# BMS_Master.net
KiCad netlist of a schematic drawn in EAGLE
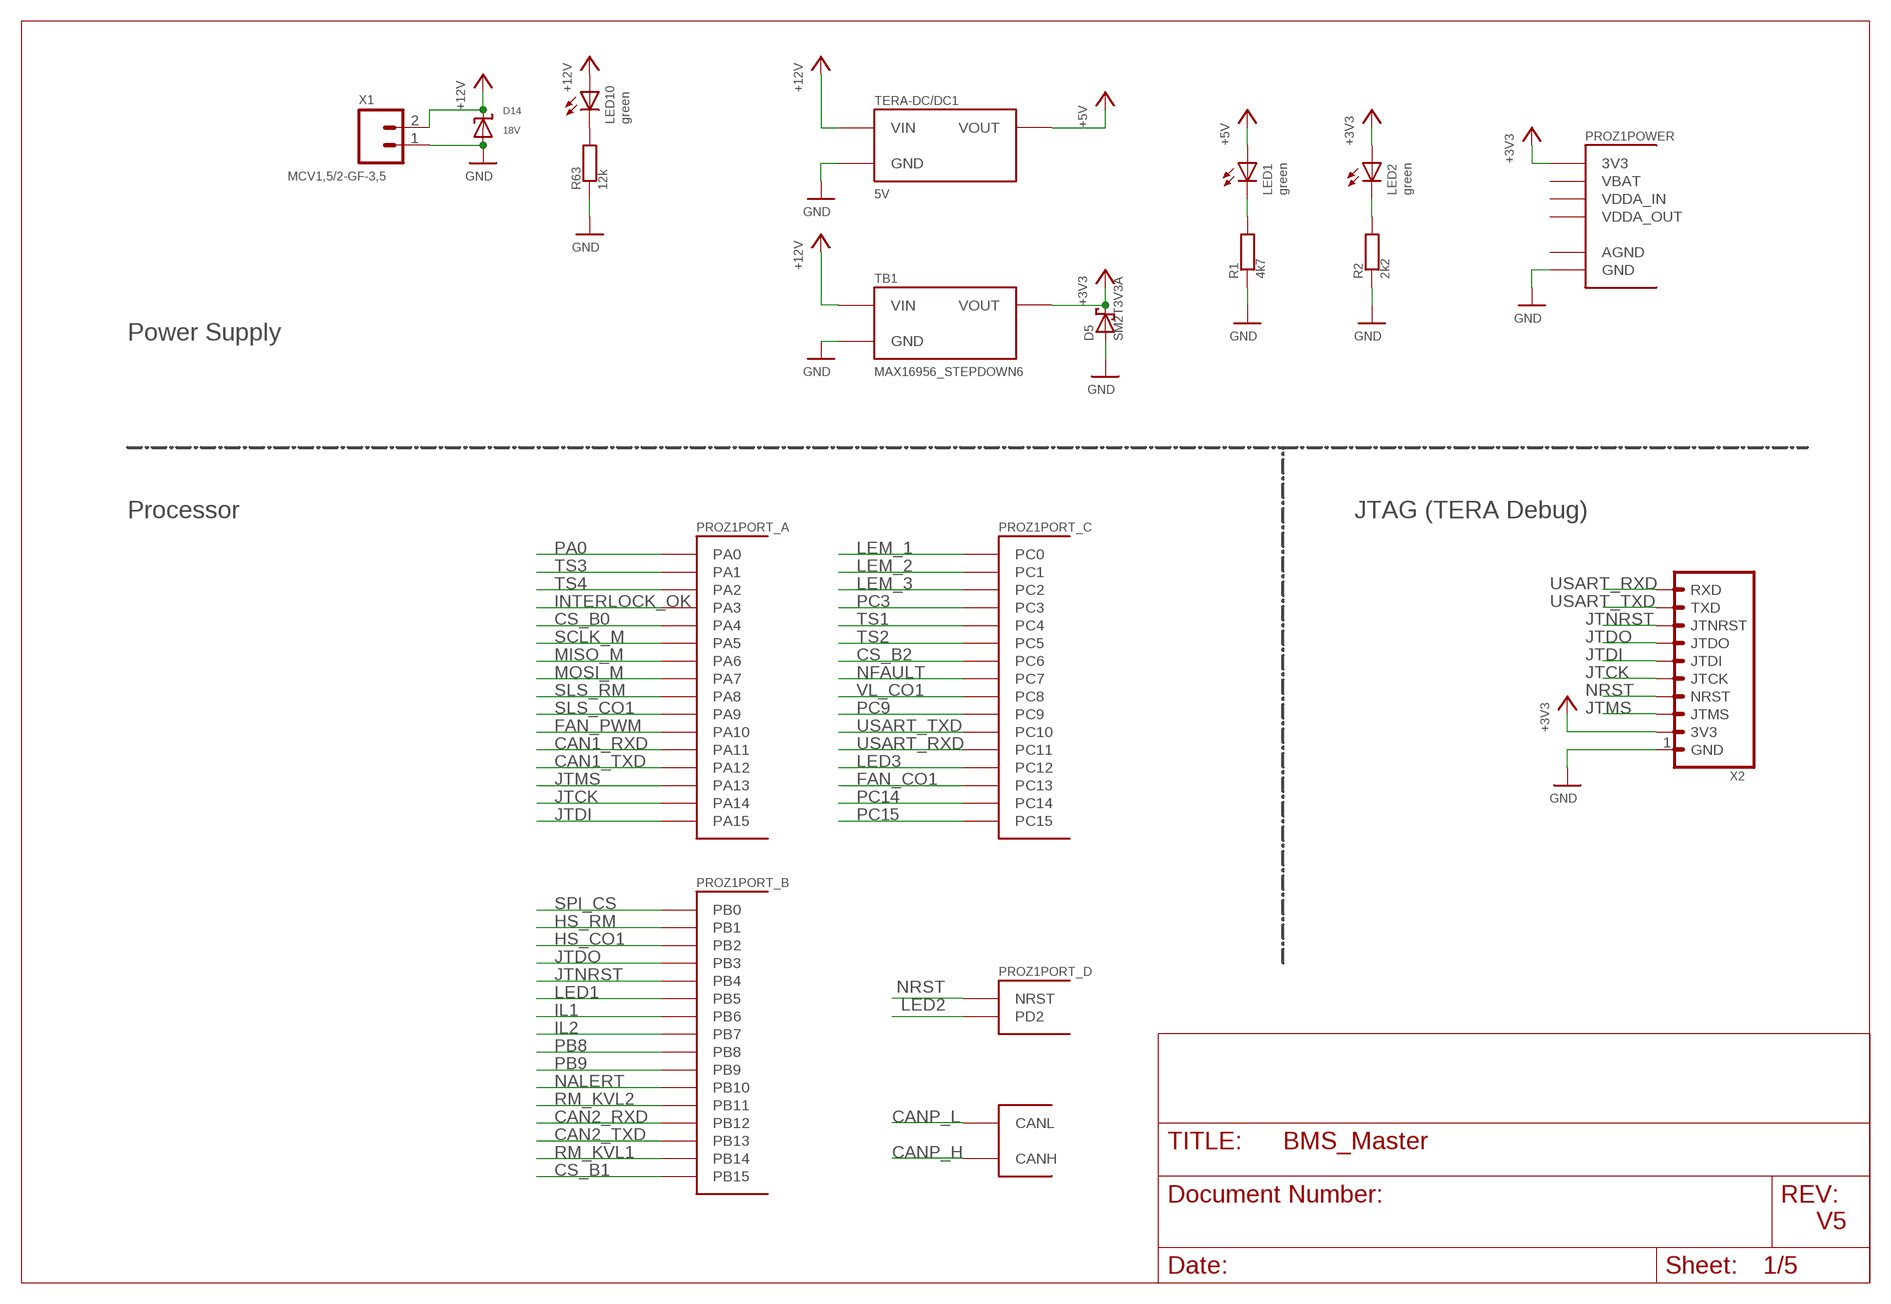
[diagram p0: schematic, sheet 1]
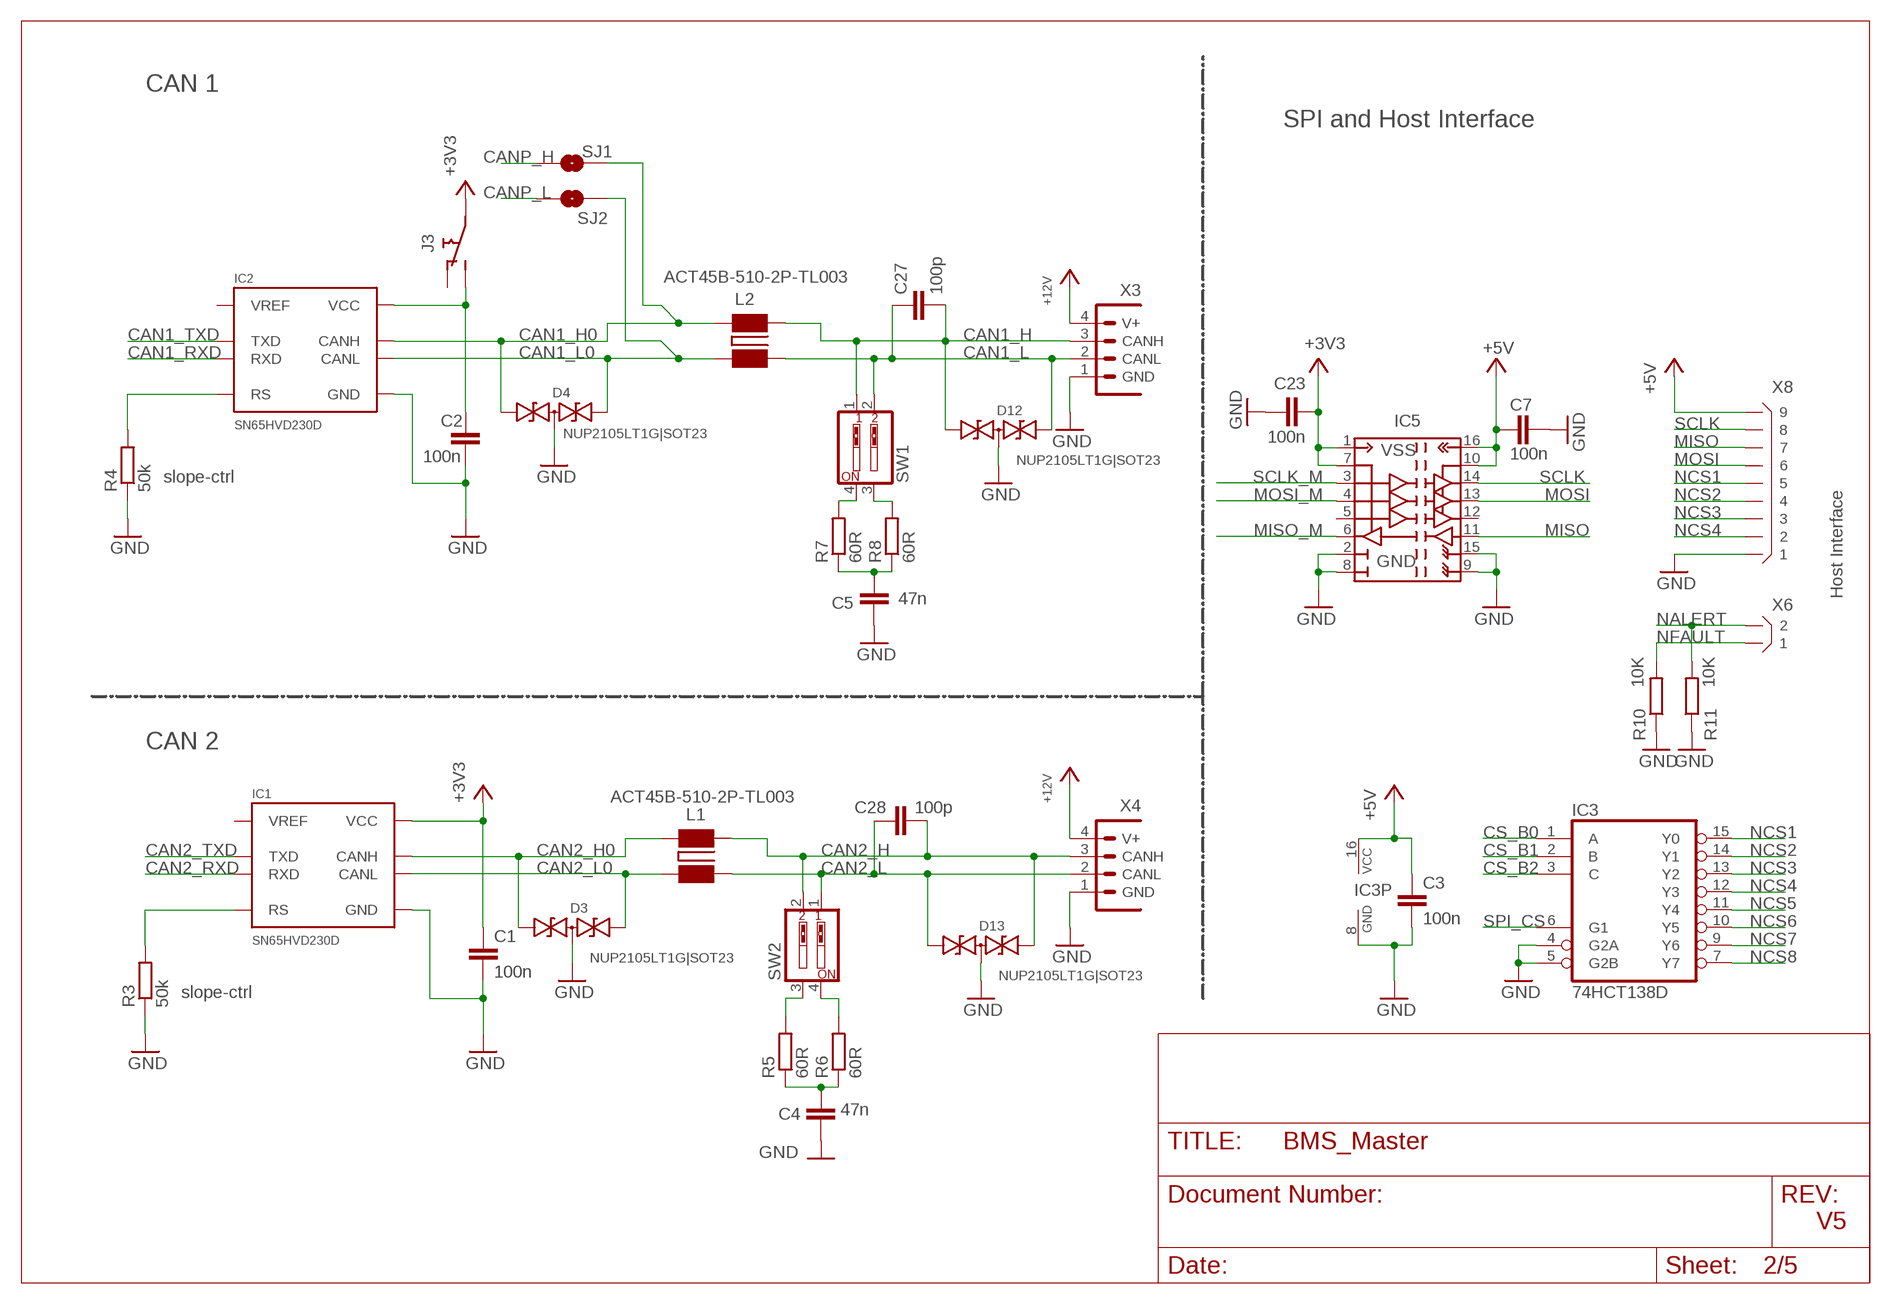
[diagram p1: schematic, sheet 2]
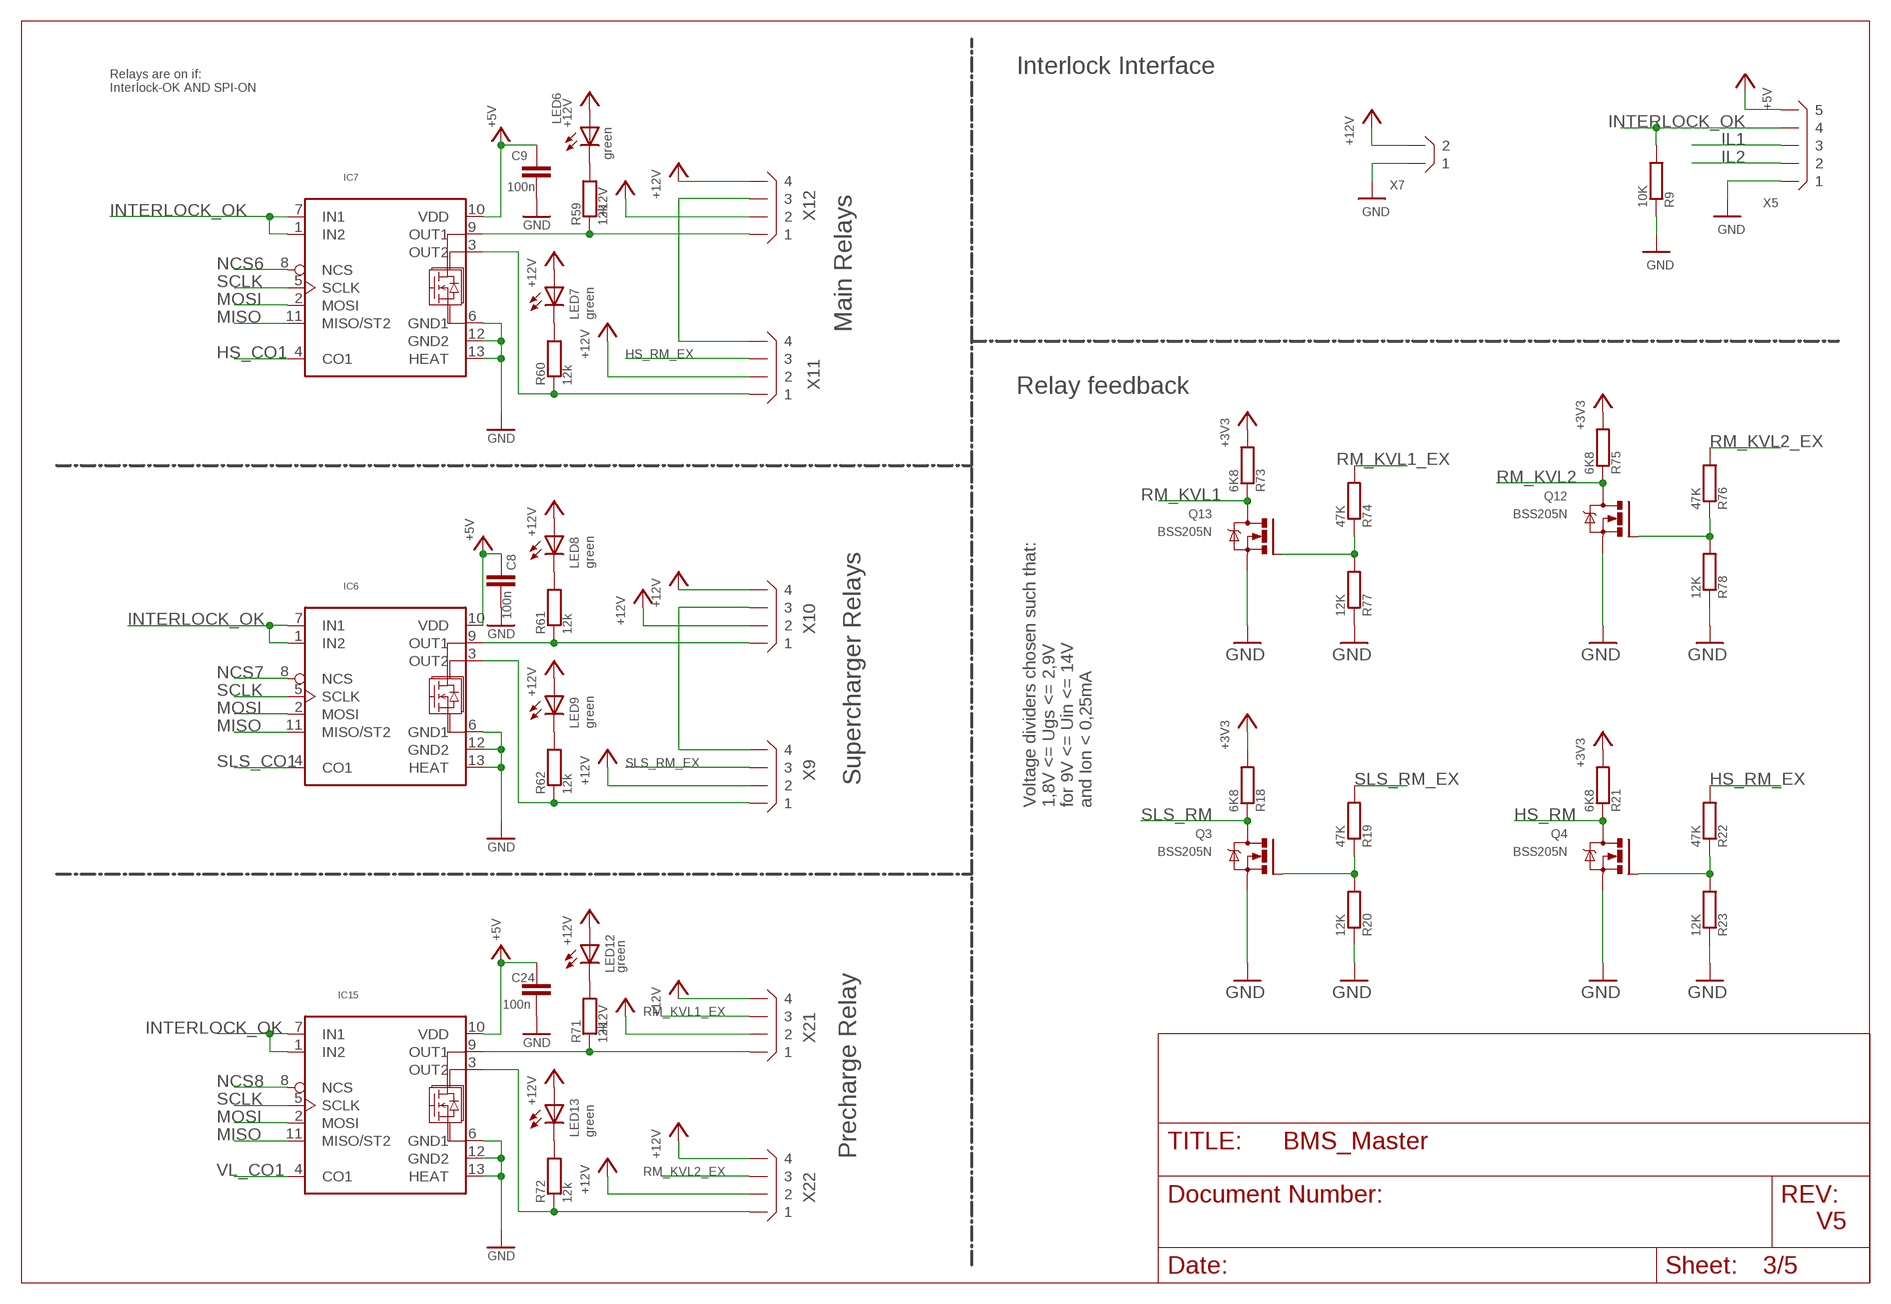
[diagram p2: schematic, sheet 3]
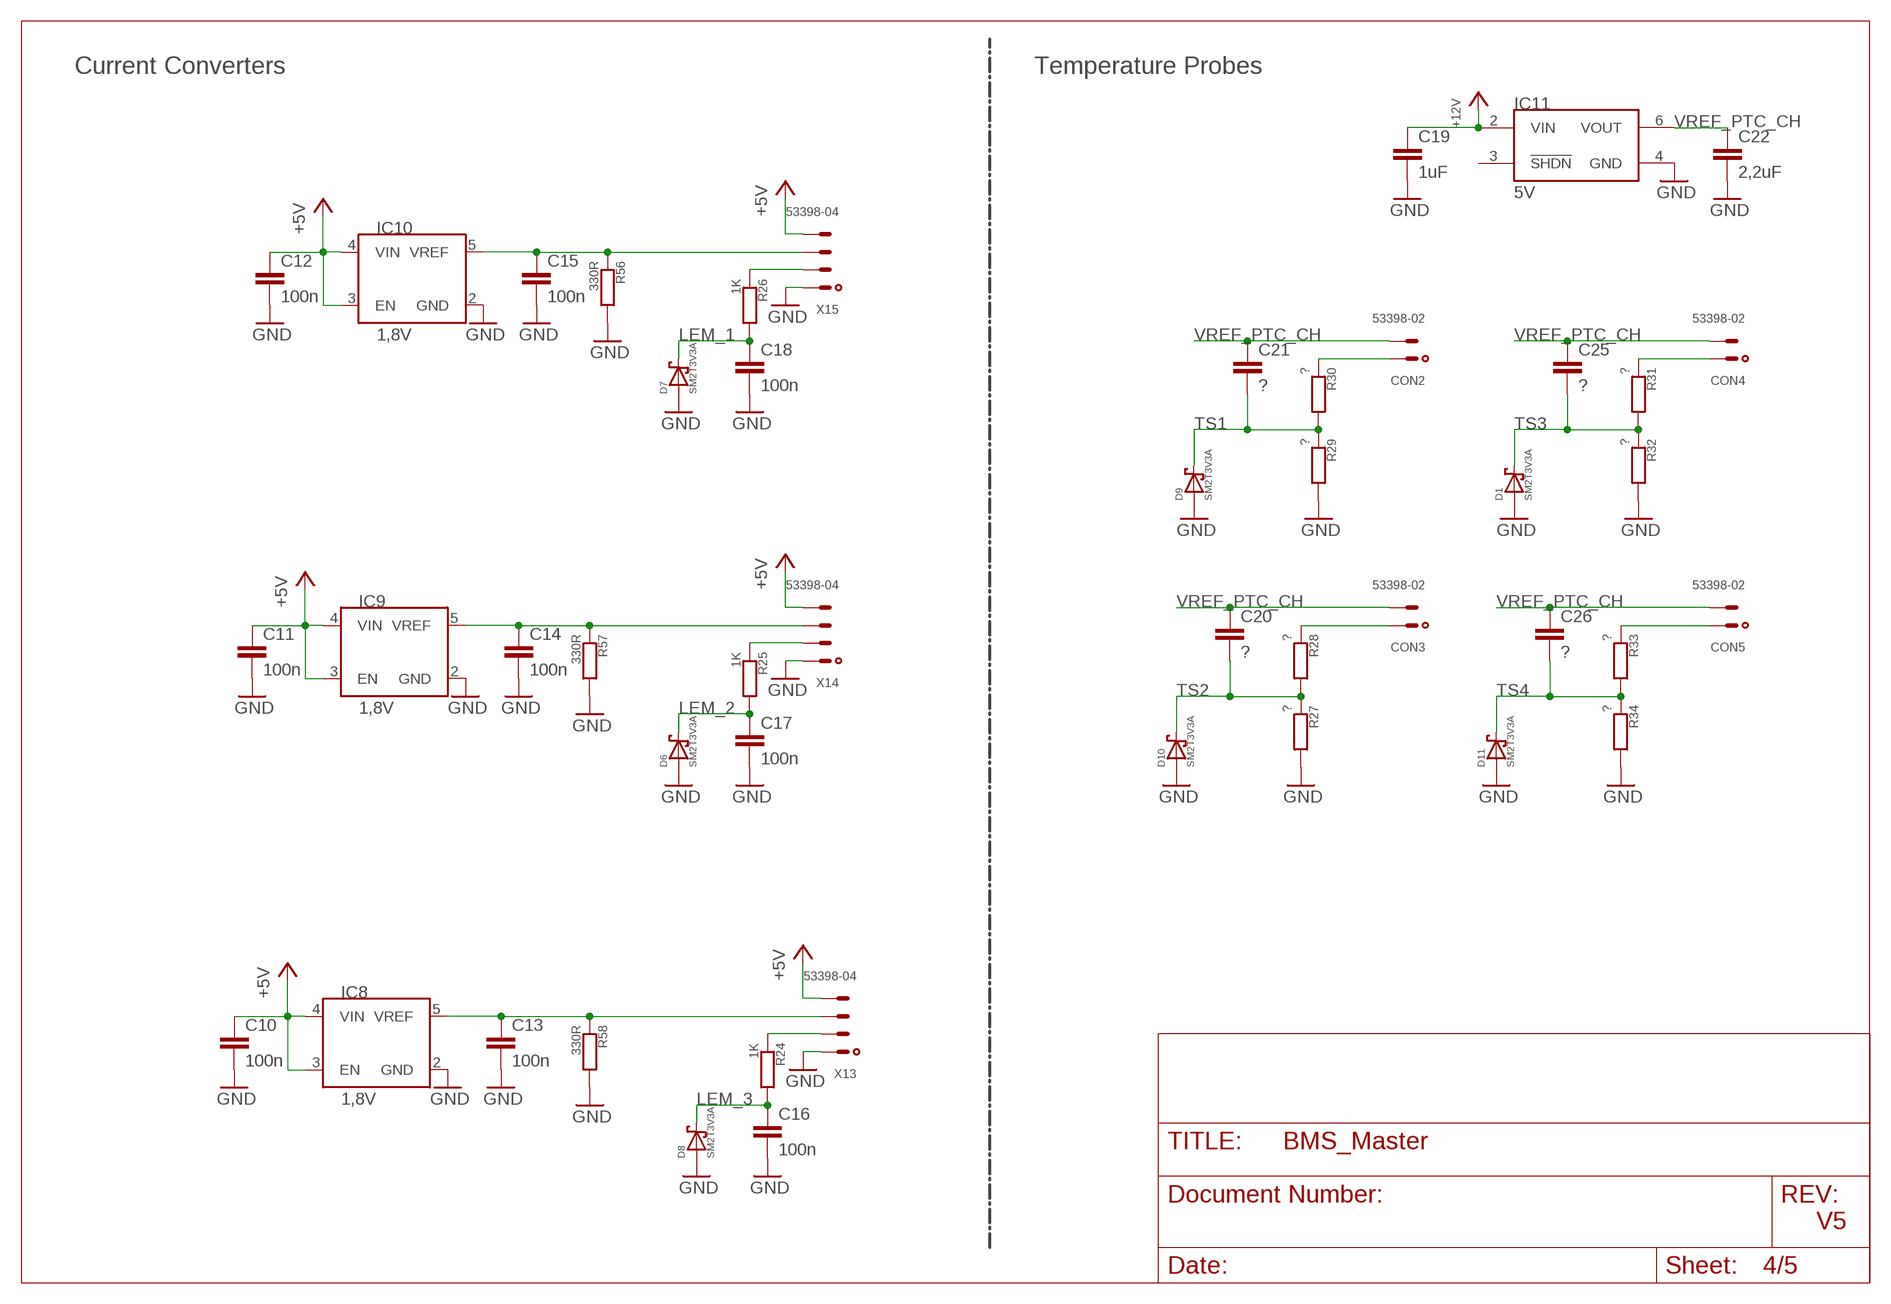
[diagram p3: schematic, sheet 4]
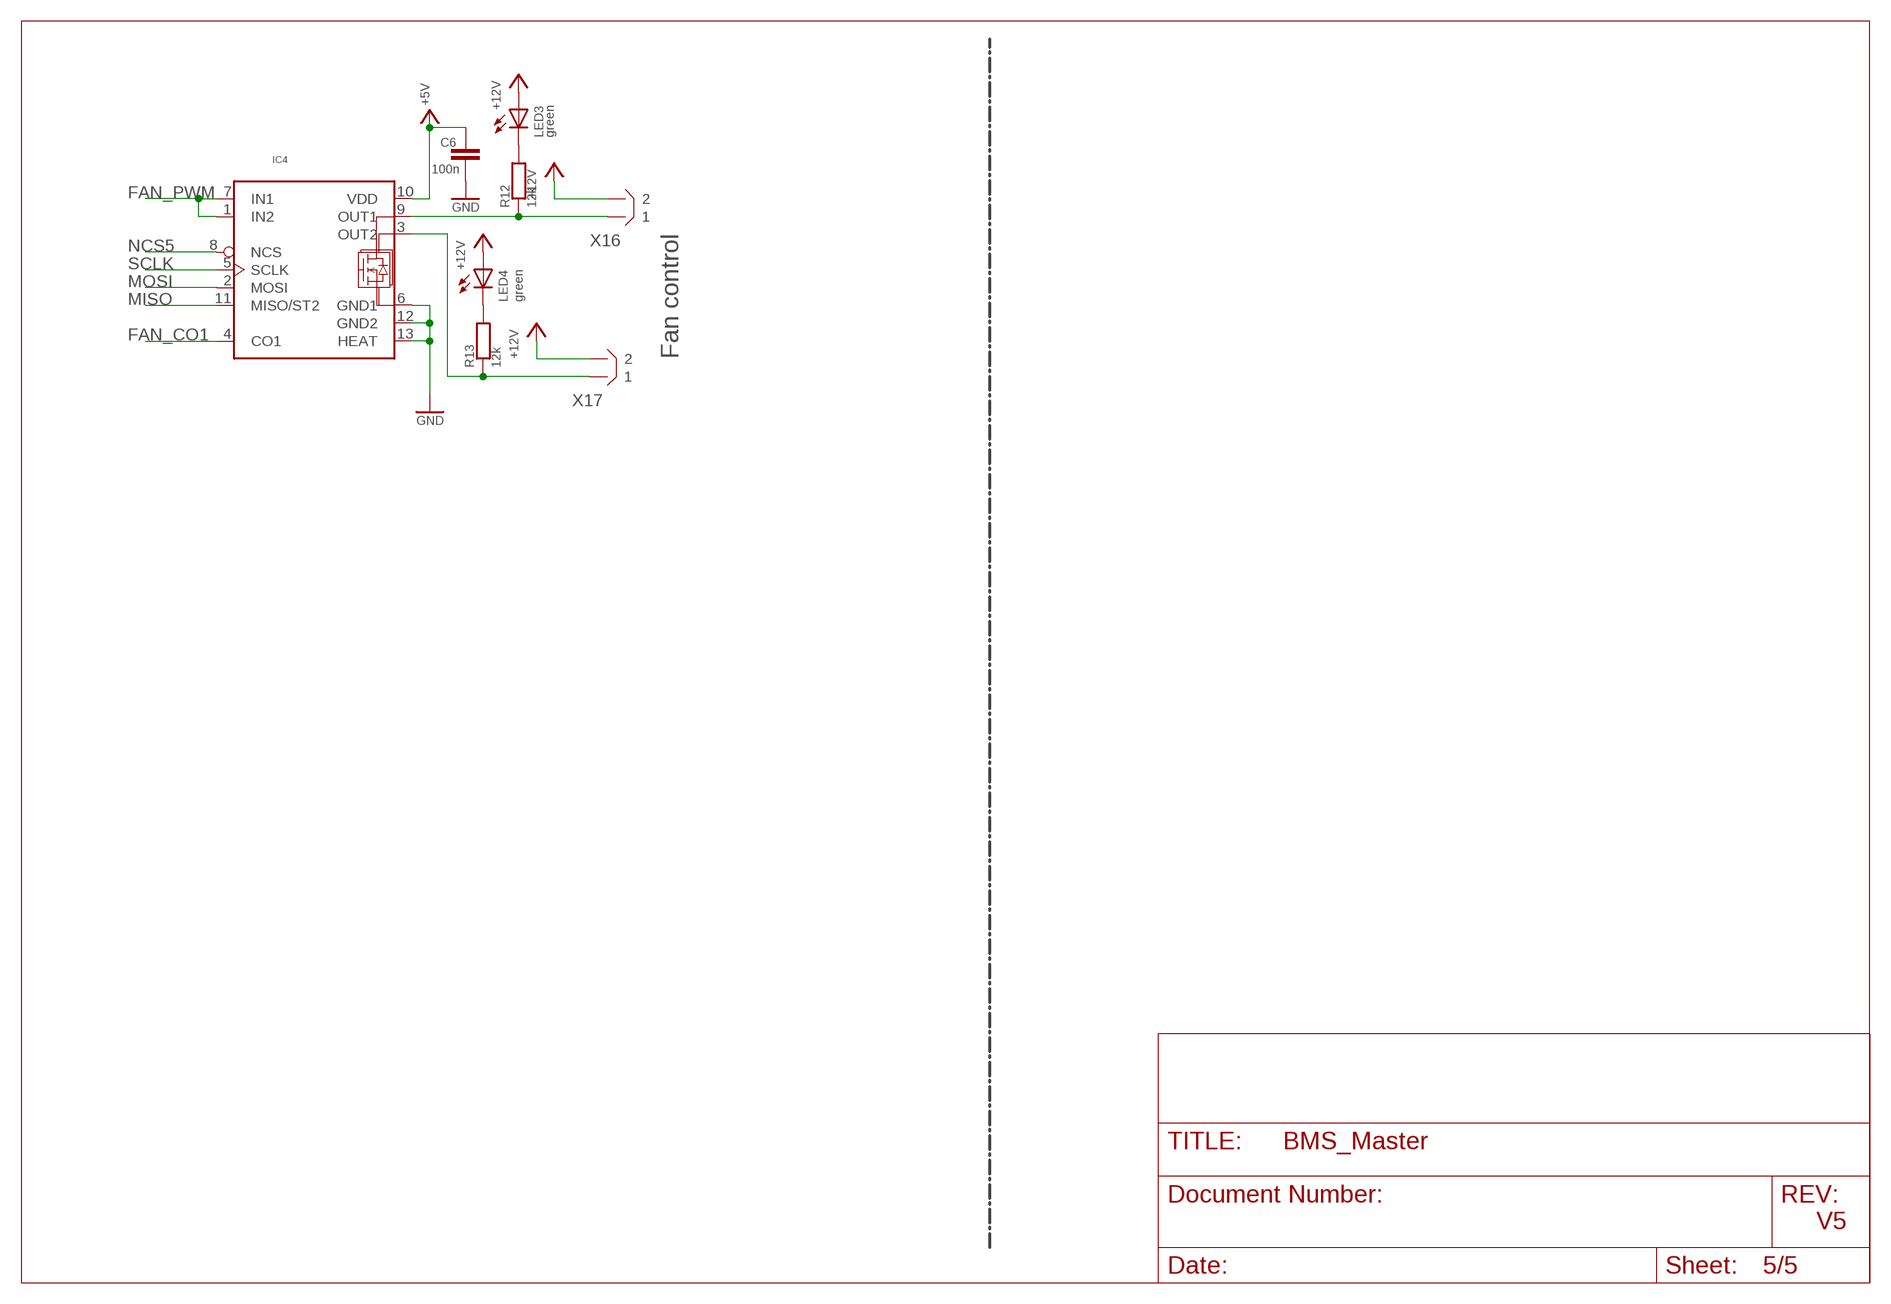
[diagram p4: schematic, sheet 5]

(export (version "E")
  (design (tool "Eeschema 10.0.6"))
  (components
    (comp (ref "C8")
      (value "100n")
      (footprint "eagle-import:C0603")
      (libsource (lib "eagle-import") (part "C-EUC0603"))
    )
    (comp (ref "C9")
      (value "100n")
      (footprint "eagle-import:C0603")
      (libsource (lib "eagle-import") (part "C-EUC0603"))
    )
    (comp (ref "C24")
      (value "100n")
      (footprint "eagle-import:C0603")
      (libsource (lib "eagle-import") (part "C-EUC0603"))
    )
    (comp (ref "IC6")
      (value "TLE8102SGN")
      (footprint "eagle-import:INF-PG-DSO-12-11_N_1PRIMARY")
      (libsource (lib "eagle-import") (part "TLE8102SGN"))
    )
    (comp (ref "IC7")
      (value "TLE8102SGN")
      (footprint "eagle-import:INF-PG-DSO-12-11_N_1PRIMARY")
      (libsource (lib "eagle-import") (part "TLE8102SGN"))
    )
    (comp (ref "IC15")
      (value "TLE8102SGN")
      (footprint "eagle-import:INF-PG-DSO-12-11_N_1PRIMARY")
      (libsource (lib "eagle-import") (part "TLE8102SGN"))
    )
    (comp (ref "LED6")
      (value "green")
      (footprint "eagle-import:CHIP-LED0805")
      (libsource (lib "eagle-import") (part "LEDCHIP-LED0805"))
    )
    (comp (ref "LED7")
      (value "green")
      (footprint "eagle-import:CHIP-LED0805")
      (libsource (lib "eagle-import") (part "LEDCHIP-LED0805"))
    )
    (comp (ref "LED8")
      (value "green")
      (footprint "eagle-import:CHIP-LED0805")
      (libsource (lib "eagle-import") (part "LEDCHIP-LED0805"))
    )
    (comp (ref "LED9")
      (value "green")
      (footprint "eagle-import:CHIP-LED0805")
      (libsource (lib "eagle-import") (part "LEDCHIP-LED0805"))
    )
    (comp (ref "LED12")
      (value "green")
      (footprint "eagle-import:CHIP-LED0805")
      (libsource (lib "eagle-import") (part "LEDCHIP-LED0805"))
    )
    (comp (ref "LED13")
      (value "green")
      (footprint "eagle-import:CHIP-LED0805")
      (libsource (lib "eagle-import") (part "LEDCHIP-LED0805"))
    )
    (comp (ref "Q3")
      (value "BSS205N")
      (footprint "eagle-import:SOT23")
      (libsource (lib "eagle-import") (part "BSS205N"))
    )
    (comp (ref "Q4")
      (value "BSS205N")
      (footprint "eagle-import:SOT23")
      (libsource (lib "eagle-import") (part "BSS205N"))
    )
    (comp (ref "Q12")
      (value "BSS205N")
      (footprint "eagle-import:SOT23")
      (libsource (lib "eagle-import") (part "BSS205N"))
    )
    (comp (ref "Q13")
      (value "BSS205N")
      (footprint "eagle-import:SOT23")
      (libsource (lib "eagle-import") (part "BSS205N"))
    )
    (comp (ref "R9")
      (value "10K")
      (footprint "eagle-import:R0805")
      (libsource (lib "eagle-import") (part "R"))
    )
    (comp (ref "R18")
      (value "6K8")
      (footprint "eagle-import:R0603")
      (libsource (lib "eagle-import") (part "R0603"))
    )
    (comp (ref "R19")
      (value "47K")
      (footprint "eagle-import:R0805")
      (libsource (lib "eagle-import") (part "R"))
    )
    (comp (ref "R20")
      (value "12K")
      (footprint "eagle-import:R0805")
      (libsource (lib "eagle-import") (part "R"))
    )
    (comp (ref "R21")
      (value "6K8")
      (footprint "eagle-import:R0603")
      (libsource (lib "eagle-import") (part "R0603"))
    )
    (comp (ref "R22")
      (value "47K")
      (footprint "eagle-import:R0805")
      (libsource (lib "eagle-import") (part "R"))
    )
    (comp (ref "R23")
      (value "12K")
      (footprint "eagle-import:R0805")
      (libsource (lib "eagle-import") (part "R"))
    )
    (comp (ref "R59")
      (value "12k")
      (footprint "eagle-import:R0805")
      (libsource (lib "eagle-import") (part "R"))
    )
    (comp (ref "R60")
      (value "12k")
      (footprint "eagle-import:R0805")
      (libsource (lib "eagle-import") (part "R"))
    )
    (comp (ref "R61")
      (value "12k")
      (footprint "eagle-import:R0805")
      (libsource (lib "eagle-import") (part "R"))
    )
    (comp (ref "R62")
      (value "12k")
      (footprint "eagle-import:R0805")
      (libsource (lib "eagle-import") (part "R"))
    )
    (comp (ref "R71")
      (value "12k")
      (footprint "eagle-import:R0805")
      (libsource (lib "eagle-import") (part "R"))
    )
    (comp (ref "R72")
      (value "12k")
      (footprint "eagle-import:R0805")
      (libsource (lib "eagle-import") (part "R"))
    )
    (comp (ref "R73")
      (value "6K8")
      (footprint "eagle-import:R0805")
      (libsource (lib "eagle-import") (part "R"))
    )
    (comp (ref "R74")
      (value "47K")
      (footprint "eagle-import:R0805")
      (libsource (lib "eagle-import") (part "R"))
    )
    (comp (ref "R75")
      (value "6K8")
      (footprint "eagle-import:R0805")
      (libsource (lib "eagle-import") (part "R"))
    )
    (comp (ref "R76")
      (value "47K")
      (footprint "eagle-import:R0805")
      (libsource (lib "eagle-import") (part "R"))
    )
    (comp (ref "R77")
      (value "12K")
      (footprint "eagle-import:R0805")
      (libsource (lib "eagle-import") (part "R"))
    )
    (comp (ref "R78")
      (value "12K")
      (footprint "eagle-import:R0805")
      (libsource (lib "eagle-import") (part "R"))
    )
    (comp (ref "X5")
      (value "B5B-XH")
      (footprint "eagle-import:B5B-XH")
      (libsource (lib "eagle-import") (part "?5B-XHB"))
    )
    (comp (ref "X7")
      (value "B2B-XH")
      (footprint "eagle-import:B2B-XH")
      (libsource (lib "eagle-import") (part "?2B-XHB"))
    )
    (comp (ref "X9")
      (value "B4B-XH")
      (footprint "eagle-import:B4B-XH")
      (libsource (lib "eagle-import") (part "?4B-XHB"))
    )
    (comp (ref "X10")
      (value "B4B-XH")
      (footprint "eagle-import:B4B-XH")
      (libsource (lib "eagle-import") (part "?4B-XHB"))
    )
    (comp (ref "X11")
      (value "B4B-XH")
      (footprint "eagle-import:B4B-XH")
      (libsource (lib "eagle-import") (part "?4B-XHB"))
    )
    (comp (ref "X12")
      (value "B4B-XH")
      (footprint "eagle-import:B4B-XH")
      (libsource (lib "eagle-import") (part "?4B-XHB"))
    )
    (comp (ref "X21")
      (value "B4B-XH")
      (footprint "eagle-import:B4B-XH")
      (libsource (lib "eagle-import") (part "?4B-XHB"))
    )
    (comp (ref "X22")
      (value "B4B-XH")
      (footprint "eagle-import:B4B-XH")
      (libsource (lib "eagle-import") (part "?4B-XHB"))
    )
    (comp (ref "C1")
      (value "100n")
      (footprint "eagle-import:C0805")
      (libsource (lib "eagle-import") (part "C-EUC0805"))
    )
    (comp (ref "C2")
      (value "100n")
      (footprint "eagle-import:C0805")
      (libsource (lib "eagle-import") (part "C-EUC0805"))
    )
    (comp (ref "C3")
      (value "100n")
      (footprint "eagle-import:C0805")
      (libsource (lib "eagle-import") (part "C-EUC0805"))
    )
    (comp (ref "C4")
      (value "47n")
      (footprint "eagle-import:C0603")
      (libsource (lib "eagle-import") (part "C-EUC0603"))
    )
    (comp (ref "C5")
      (value "47n")
      (footprint "eagle-import:C0603")
      (libsource (lib "eagle-import") (part "C-EUC0603"))
    )
    (comp (ref "C7")
      (value "100n")
      (footprint "eagle-import:C0603")
      (libsource (lib "eagle-import") (part "C0603"))
    )
    (comp (ref "C23")
      (value "100n")
      (footprint "eagle-import:C0603")
      (libsource (lib "eagle-import") (part "C0603"))
    )
    (comp (ref "C27")
      (value "100p")
      (footprint "eagle-import:C0603")
      (libsource (lib "eagle-import") (part "C-EUC0603"))
    )
    (comp (ref "C28")
      (value "100p")
      (footprint "eagle-import:C0603")
      (libsource (lib "eagle-import") (part "C-EUC0603"))
    )
    (comp (ref "D3")
      (value "NUP2105LT1G|SOT23")
      (footprint "eagle-import:SOT23")
      (libsource (lib "eagle-import") (part "NUP2105LT1G|SOT23"))
    )
    (comp (ref "D4")
      (value "NUP2105LT1G|SOT23")
      (footprint "eagle-import:SOT23")
      (libsource (lib "eagle-import") (part "NUP2105LT1G|SOT23"))
    )
    (comp (ref "D12")
      (value "NUP2105LT1G|SOT23")
      (footprint "eagle-import:SOT23")
      (libsource (lib "eagle-import") (part "NUP2105LT1G|SOT23"))
    )
    (comp (ref "D13")
      (value "NUP2105LT1G|SOT23")
      (footprint "eagle-import:SOT23")
      (libsource (lib "eagle-import") (part "NUP2105LT1G|SOT23"))
    )
    (comp (ref "IC1")
      (value "SN65HVD230D")
      (footprint "eagle-import:SO08")
      (libsource (lib "eagle-import") (part "SN65HVD23D0"))
    )
    (comp (ref "IC2")
      (value "SN65HVD230D")
      (footprint "eagle-import:SO08")
      (libsource (lib "eagle-import") (part "SN65HVD23D0"))
    )
    (comp (ref "IC3")
      (value "74HCT138D")
      (footprint "eagle-import:SO16")
      (libsource (lib "eagle-import") (part "74138DHCT"))
    )
    (comp (ref "IC5")
      (value "ISO7241")
      (footprint "eagle-import:R-PDSO-G16")
      (libsource (lib "eagle-import") (part "ISO7241"))
    )
    (comp (ref "J3")
      (value "JUMPER_SWITCHS")
      (footprint "eagle-import:J_OR_S")
      (libsource (lib "eagle-import") (part "JUMPER_SWITCHS"))
    )
    (comp (ref "L1")
      (value "ACT45B-510-2P-TL003")
      (footprint "eagle-import:ACT45B")
      (libsource (lib "eagle-import") (part "ACT45B-510-2P-TL003"))
    )
    (comp (ref "L2")
      (value "ACT45B-510-2P-TL003")
      (footprint "eagle-import:ACT45B")
      (libsource (lib "eagle-import") (part "ACT45B-510-2P-TL003"))
    )
    (comp (ref "R3")
      (value "50k")
      (footprint "eagle-import:R0805")
      (libsource (lib "eagle-import") (part "R-EU_R0805"))
    )
    (comp (ref "R4")
      (value "50k")
      (footprint "eagle-import:R0805")
      (libsource (lib "eagle-import") (part "R-EU_R0805"))
    )
    (comp (ref "R5")
      (value "60R")
      (footprint "eagle-import:R0603")
      (libsource (lib "eagle-import") (part "R-EU_R0603"))
    )
    (comp (ref "R6")
      (value "60R")
      (footprint "eagle-import:R0603")
      (libsource (lib "eagle-import") (part "R-EU_R0603"))
    )
    (comp (ref "R7")
      (value "60R")
      (footprint "eagle-import:R0603")
      (libsource (lib "eagle-import") (part "R-EU_R0603"))
    )
    (comp (ref "R8")
      (value "60R")
      (footprint "eagle-import:R0603")
      (libsource (lib "eagle-import") (part "R-EU_R0603"))
    )
    (comp (ref "R10")
      (value "10K")
      (footprint "eagle-import:R0603")
      (libsource (lib "eagle-import") (part "R-EU_R0603"))
    )
    (comp (ref "R11")
      (value "10K")
      (footprint "eagle-import:R0603")
      (libsource (lib "eagle-import") (part "R-EU_R0603"))
    )
    (comp (ref "SJ1")
      (value "SOLDERJUMPERNO")
      (footprint "eagle-import:SJ_2S-NO")
      (libsource (lib "eagle-import") (part "SOLDERJUMPERNO"))
    )
    (comp (ref "SJ2")
      (value "SOLDERJUMPERNO")
      (footprint "eagle-import:SJ_2S-NO")
      (libsource (lib "eagle-import") (part "SOLDERJUMPERNO"))
    )
    (comp (ref "SW1")
      (value "DIP_SWITCH_DIP2")
      (footprint "eagle-import:DIPSWITCH-02")
      (libsource (lib "eagle-import") (part "DIP_SWITCH_DIP2"))
    )
    (comp (ref "SW2")
      (value "DIP_SWITCH_DIP2")
      (footprint "eagle-import:DIPSWITCH-02")
      (libsource (lib "eagle-import") (part "DIP_SWITCH_DIP2"))
    )
    (comp (ref "X3")
      (value "CIOC_4-1-FV-A_CAN-BELEGUNG")
      (footprint "eagle-import:CIOC_4-1-FV")
      (libsource (lib "eagle-import") (part "CIOC_4-1-FV-A_CAN-BELEGUNG"))
    )
    (comp (ref "X4")
      (value "CIOC_4-1-FV-A_CAN-BELEGUNG")
      (footprint "eagle-import:CIOC_4-1-FV")
      (libsource (lib "eagle-import") (part "CIOC_4-1-FV-A_CAN-BELEGUNG"))
    )
    (comp (ref "X6")
      (value "B2B-XH")
      (footprint "eagle-import:B2B-XH")
      (libsource (lib "eagle-import") (part "?2B-XHB"))
    )
    (comp (ref "X8")
      (value "B9B-XH")
      (footprint "eagle-import:B9B-XH")
      (libsource (lib "eagle-import") (part "?9B-XHB"))
    )
    (comp (ref "D5")
      (value "SM2T3V3A")
      (footprint "eagle-import:SM2T3V3A")
      (libsource (lib "eagle-import") (part "SM2T3V3A"))
    )
    (comp (ref "D14")
      (value "18V")
      (footprint "eagle-import:SMBJ")
      (libsource (lib "eagle-import") (part "SUPPRESSOR-SMBJ"))
    )
    (comp (ref "LED1")
      (value "green")
      (footprint "eagle-import:CHIP-LED0805")
      (libsource (lib "eagle-import") (part "LEDCHIP-LED0805"))
    )
    (comp (ref "LED2")
      (value "green")
      (footprint "eagle-import:CHIP-LED0805")
      (libsource (lib "eagle-import") (part "LEDCHIP-LED0805"))
    )
    (comp (ref "LED10")
      (value "green")
      (footprint "eagle-import:CHIP-LED0805")
      (libsource (lib "eagle-import") (part "LEDCHIP-LED0805"))
    )
    (comp (ref "PROZ1")
      (value "STM32F4_PROZESSORBOARDRPZ")
      (footprint "eagle-import:STM32F4_PROZESSORBOARD")
      (libsource (lib "eagle-import") (part "STM32F4_PROZESSORBOARDRPZ"))
    )
    (comp (ref "R1")
      (value "4k7")
      (footprint "eagle-import:R0805")
      (libsource (lib "eagle-import") (part "R"))
    )
    (comp (ref "R2")
      (value "2k2")
      (footprint "eagle-import:R0805")
      (libsource (lib "eagle-import") (part "R"))
    )
    (comp (ref "R63")
      (value "12k")
      (footprint "eagle-import:R0805")
      (libsource (lib "eagle-import") (part "R"))
    )
    (comp (ref "TB1")
      (value "MAX16956_STEPDOWN6")
      (footprint "eagle-import:MAX16956_STEPDOWN6")
      (libsource (lib "eagle-import") (part "MAX16956_STEPDOWN6"))
    )
    (comp (ref "TERA-DC/DC1")
      (value "5V")
      (footprint "eagle-import:MAX5035_STEPDOWN3")
      (libsource (lib "eagle-import") (part "MAX5035_STEPDOWN3"))
    )
    (comp (ref "X1")
      (value "MCV1,5/2-GF-3,5")
      (footprint "eagle-import:MCV1,5_2-GF-3,5")
      (libsource (lib "eagle-import") (part "MCV1,5/2-GF-3,5"))
    )
    (comp (ref "X2")
      (value "TERA-PROG-DEBUG-10GERADE")
      (footprint "eagle-import:90130-1110")
      (libsource (lib "eagle-import") (part "TERA-PROG-DEBUG-10GERADE"))
    )
    (comp (ref "C10")
      (value "100n")
      (footprint "eagle-import:C0805")
      (libsource (lib "eagle-import") (part "C-EUC0805"))
    )
    (comp (ref "C11")
      (value "100n")
      (footprint "eagle-import:C0805")
      (libsource (lib "eagle-import") (part "C-EUC0805"))
    )
    (comp (ref "C12")
      (value "100n")
      (footprint "eagle-import:C0805")
      (libsource (lib "eagle-import") (part "C-EUC0805"))
    )
    (comp (ref "C13")
      (value "100n")
      (footprint "eagle-import:C0805")
      (libsource (lib "eagle-import") (part "C-EUC0805"))
    )
    (comp (ref "C14")
      (value "100n")
      (footprint "eagle-import:C0805")
      (libsource (lib "eagle-import") (part "C-EUC0805"))
    )
    (comp (ref "C15")
      (value "100n")
      (footprint "eagle-import:C0805")
      (libsource (lib "eagle-import") (part "C-EUC0805"))
    )
    (comp (ref "C16")
      (value "100n")
      (footprint "eagle-import:C0805")
      (libsource (lib "eagle-import") (part "C-EUC0805"))
    )
    (comp (ref "C17")
      (value "100n")
      (footprint "eagle-import:C0805")
      (libsource (lib "eagle-import") (part "C-EUC0805"))
    )
    (comp (ref "C18")
      (value "100n")
      (footprint "eagle-import:C0805")
      (libsource (lib "eagle-import") (part "C-EUC0805"))
    )
    (comp (ref "C19")
      (value "1uF")
      (footprint "eagle-import:C0805")
      (libsource (lib "eagle-import") (part "C-EUC0805"))
    )
    (comp (ref "C20")
      (value "?")
      (footprint "eagle-import:C0603")
      (libsource (lib "eagle-import") (part "C-EUC0603"))
    )
    (comp (ref "C21")
      (value "?")
      (footprint "eagle-import:C0603")
      (libsource (lib "eagle-import") (part "C-EUC0603"))
    )
    (comp (ref "C22")
      (value "2,2uF")
      (footprint "eagle-import:C0805")
      (libsource (lib "eagle-import") (part "C-EUC0805"))
    )
    (comp (ref "C25")
      (value "?")
      (footprint "eagle-import:C0603")
      (libsource (lib "eagle-import") (part "C-EUC0603"))
    )
    (comp (ref "C26")
      (value "?")
      (footprint "eagle-import:C0603")
      (libsource (lib "eagle-import") (part "C-EUC0603"))
    )
    (comp (ref "CON2")
      (value "53398-02")
      (footprint "eagle-import:53398-02")
      (libsource (lib "eagle-import") (part "53?-02398"))
    )
    (comp (ref "CON3")
      (value "53398-02")
      (footprint "eagle-import:53398-02")
      (libsource (lib "eagle-import") (part "53?-02398"))
    )
    (comp (ref "CON4")
      (value "53398-02")
      (footprint "eagle-import:53398-02")
      (libsource (lib "eagle-import") (part "53?-02398"))
    )
    (comp (ref "CON5")
      (value "53398-02")
      (footprint "eagle-import:53398-02")
      (libsource (lib "eagle-import") (part "53?-02398"))
    )
    (comp (ref "D1")
      (value "SM2T3V3A")
      (footprint "eagle-import:SM2T3V3A")
      (libsource (lib "eagle-import") (part "SM2T3V3A"))
    )
    (comp (ref "D6")
      (value "SM2T3V3A")
      (footprint "eagle-import:SM2T3V3A")
      (libsource (lib "eagle-import") (part "SM2T3V3A"))
    )
    (comp (ref "D7")
      (value "SM2T3V3A")
      (footprint "eagle-import:SM2T3V3A")
      (libsource (lib "eagle-import") (part "SM2T3V3A"))
    )
    (comp (ref "D8")
      (value "SM2T3V3A")
      (footprint "eagle-import:SM2T3V3A")
      (libsource (lib "eagle-import") (part "SM2T3V3A"))
    )
    (comp (ref "D9")
      (value "SM2T3V3A")
      (footprint "eagle-import:SM2T3V3A")
      (libsource (lib "eagle-import") (part "SM2T3V3A"))
    )
    (comp (ref "D10")
      (value "SM2T3V3A")
      (footprint "eagle-import:SM2T3V3A")
      (libsource (lib "eagle-import") (part "SM2T3V3A"))
    )
    (comp (ref "D11")
      (value "SM2T3V3A")
      (footprint "eagle-import:SM2T3V3A")
      (libsource (lib "eagle-import") (part "SM2T3V3A"))
    )
    (comp (ref "IC8")
      (value "1,8V")
      (footprint "eagle-import:SOT23-5L")
      (libsource (lib "eagle-import") (part "LM4132L"))
    )
    (comp (ref "IC9")
      (value "1,8V")
      (footprint "eagle-import:SOT23-5L")
      (libsource (lib "eagle-import") (part "LM4132L"))
    )
    (comp (ref "IC10")
      (value "1,8V")
      (footprint "eagle-import:SOT23-5L")
      (libsource (lib "eagle-import") (part "LM4132L"))
    )
    (comp (ref "IC11")
      (value "5V")
      (footprint "eagle-import:SO08")
      (libsource (lib "eagle-import") (part "LT1461"))
    )
    (comp (ref "R24")
      (value "1K")
      (footprint "eagle-import:R0805")
      (libsource (lib "eagle-import") (part "R"))
    )
    (comp (ref "R25")
      (value "1K")
      (footprint "eagle-import:R0805")
      (libsource (lib "eagle-import") (part "R"))
    )
    (comp (ref "R26")
      (value "1K")
      (footprint "eagle-import:R0805")
      (libsource (lib "eagle-import") (part "R"))
    )
    (comp (ref "R27")
      (value "?")
      (footprint "eagle-import:R0603")
      (libsource (lib "eagle-import") (part "R0603"))
    )
    (comp (ref "R28")
      (value "?")
      (footprint "eagle-import:R0603")
      (libsource (lib "eagle-import") (part "R0603"))
    )
    (comp (ref "R29")
      (value "?")
      (footprint "eagle-import:R0603")
      (libsource (lib "eagle-import") (part "R0603"))
    )
    (comp (ref "R30")
      (value "?")
      (footprint "eagle-import:R0603")
      (libsource (lib "eagle-import") (part "R0603"))
    )
    (comp (ref "R31")
      (value "?")
      (footprint "eagle-import:R0603")
      (libsource (lib "eagle-import") (part "R0603"))
    )
    (comp (ref "R32")
      (value "?")
      (footprint "eagle-import:R0603")
      (libsource (lib "eagle-import") (part "R0603"))
    )
    (comp (ref "R33")
      (value "?")
      (footprint "eagle-import:R0603")
      (libsource (lib "eagle-import") (part "R0603"))
    )
    (comp (ref "R34")
      (value "?")
      (footprint "eagle-import:R0603")
      (libsource (lib "eagle-import") (part "R0603"))
    )
    (comp (ref "R56")
      (value "330R")
      (footprint "eagle-import:R0805")
      (libsource (lib "eagle-import") (part "R"))
    )
    (comp (ref "R57")
      (value "330R")
      (footprint "eagle-import:R0805")
      (libsource (lib "eagle-import") (part "R"))
    )
    (comp (ref "R58")
      (value "330R")
      (footprint "eagle-import:R0805")
      (libsource (lib "eagle-import") (part "R"))
    )
    (comp (ref "X13")
      (value "53398-04")
      (footprint "eagle-import:53398-04")
      (libsource (lib "eagle-import") (part "53?-04398"))
    )
    (comp (ref "X14")
      (value "53398-04")
      (footprint "eagle-import:53398-04")
      (libsource (lib "eagle-import") (part "53?-04398"))
    )
    (comp (ref "X15")
      (value "53398-04")
      (footprint "eagle-import:53398-04")
      (libsource (lib "eagle-import") (part "53?-04398"))
    )
    (comp (ref "C6")
      (value "100n")
      (footprint "eagle-import:C0603")
      (libsource (lib "eagle-import") (part "C-EUC0603"))
    )
    (comp (ref "IC4")
      (value "TLE8102SGN")
      (footprint "eagle-import:INF-PG-DSO-12-11_N_1PRIMARY")
      (libsource (lib "eagle-import") (part "TLE8102SGN"))
    )
    (comp (ref "LED3")
      (value "green")
      (footprint "eagle-import:CHIP-LED0805")
      (libsource (lib "eagle-import") (part "LEDCHIP-LED0805"))
    )
    (comp (ref "LED4")
      (value "green")
      (footprint "eagle-import:CHIP-LED0805")
      (libsource (lib "eagle-import") (part "LEDCHIP-LED0805"))
    )
    (comp (ref "R12")
      (value "12k")
      (footprint "eagle-import:R0805")
      (libsource (lib "eagle-import") (part "R"))
    )
    (comp (ref "R13")
      (value "12k")
      (footprint "eagle-import:R0805")
      (libsource (lib "eagle-import") (part "R"))
    )
    (comp (ref "X16")
      (value "B2B-XH")
      (footprint "eagle-import:B2B-XH")
      (libsource (lib "eagle-import") (part "?2B-XHB"))
    )
    (comp (ref "X17")
      (value "B2B-XH")
      (footprint "eagle-import:B2B-XH")
      (libsource (lib "eagle-import") (part "?2B-XHB"))
    )
  )
  (nets
    (net (code "1") (name "+3V3") (class "Default")
      (node (ref "C1") (pin "1") (pinfunction "1_1") (pintype "passive"))
      (node (ref "C23") (pin "2") (pinfunction "2_2") (pintype "passive"))
      (node (ref "D5") (pin "P$2") (pinfunction "P$2_P$2") (pintype "bidirectional"))
      (node (ref "IC1") (pin "3") (pinfunction "VCC_3") (pintype "power_in"))
      (node (ref "IC5") (pin "1") (pinfunction "VCC1_1") (pintype "bidirectional"))
      (node (ref "IC5") (pin "7") (pinfunction "EN1_7") (pintype "bidirectional"))
      (node (ref "J3") (pin "P$1") (pinfunction "P$1_P$1") (pintype "bidirectional"))
      (node (ref "LED2") (pin "A") (pinfunction "A_A") (pintype "passive"))
      (node (ref "PROZ1") (pin "45") (pinfunction "3V3_45") (pintype "passive"))
      (node (ref "PROZ1") (pin "46") (pinfunction "3V3_46") (pintype "passive"))
      (node (ref "R18") (pin "2") (pinfunction "2_2") (pintype "passive"))
      (node (ref "R21") (pin "2") (pinfunction "2_2") (pintype "passive"))
      (node (ref "R73") (pin "2") (pinfunction "2_2") (pintype "passive"))
      (node (ref "R75") (pin "2") (pinfunction "2_2") (pintype "passive"))
      (node (ref "TB1") (pin "VOUT") (pinfunction "VOUT_VOUT") (pintype "passive"))
      (node (ref "X2") (pin "2") (pinfunction "3V3_2") (pintype "passive"))
    )
    (net (code "2") (name "+5V") (class "Default")
      (node (ref "C10") (pin "1") (pinfunction "1_1") (pintype "passive"))
      (node (ref "C11") (pin "1") (pinfunction "1_1") (pintype "passive"))
      (node (ref "C12") (pin "1") (pinfunction "1_1") (pintype "passive"))
      (node (ref "C24") (pin "1") (pinfunction "1_1") (pintype "passive"))
      (node (ref "C3") (pin "1") (pinfunction "1_1") (pintype "passive"))
      (node (ref "C6") (pin "1") (pinfunction "1_1") (pintype "passive"))
      (node (ref "C7") (pin "2") (pinfunction "2_2") (pintype "passive"))
      (node (ref "C8") (pin "1") (pinfunction "1_1") (pintype "passive"))
      (node (ref "C9") (pin "1") (pinfunction "1_1") (pintype "passive"))
      (node (ref "IC10") (pin "3") (pinfunction "EN_3") (pintype "bidirectional"))
      (node (ref "IC10") (pin "4") (pinfunction "VIN_4") (pintype "bidirectional"))
      (node (ref "IC15") (pin "10") (pinfunction "VDD_10") (pintype "bidirectional"))
      (node (ref "IC3") (pin "16") (pinfunction "VCC_16") (pintype "power_in"))
      (node (ref "IC4") (pin "10") (pinfunction "VDD_10") (pintype "bidirectional"))
      (node (ref "IC5") (pin "10") (pinfunction "EN2_10") (pintype "bidirectional"))
      (node (ref "IC5") (pin "16") (pinfunction "VCC2_16") (pintype "bidirectional"))
      (node (ref "IC6") (pin "10") (pinfunction "VDD_10") (pintype "bidirectional"))
      (node (ref "IC7") (pin "10") (pinfunction "VDD_10") (pintype "bidirectional"))
      (node (ref "IC8") (pin "3") (pinfunction "EN_3") (pintype "bidirectional"))
      (node (ref "IC8") (pin "4") (pinfunction "VIN_4") (pintype "bidirectional"))
      (node (ref "IC9") (pin "3") (pinfunction "EN_3") (pintype "bidirectional"))
      (node (ref "IC9") (pin "4") (pinfunction "VIN_4") (pintype "bidirectional"))
      (node (ref "LED1") (pin "A") (pinfunction "A_A") (pintype "passive"))
      (node (ref "TERA-DC/DC1") (pin "VOUT") (pinfunction "VOUT_VOUT") (pintype "passive"))
      (node (ref "X13") (pin "4") (pinfunction "4_4") (pintype "passive"))
      (node (ref "X14") (pin "4") (pinfunction "4_4") (pintype "passive"))
      (node (ref "X15") (pin "4") (pinfunction "4_4") (pintype "passive"))
      (node (ref "X5") (pin "P$5") (pinfunction "5_P$5") (pintype "bidirectional"))
      (node (ref "X8") (pin "P$9") (pinfunction "9_P$9") (pintype "bidirectional"))
    )
    (net (code "3") (name "+12V") (class "Default")
      (node (ref "C19") (pin "1") (pinfunction "1_1") (pintype "passive"))
      (node (ref "D14") (pin "C") (pinfunction "C_C") (pintype "passive"))
      (node (ref "IC11") (pin "2") (pinfunction "VIN_2") (pintype "passive"))
      (node (ref "LED10") (pin "A") (pinfunction "A_A") (pintype "passive"))
      (node (ref "LED12") (pin "A") (pinfunction "A_A") (pintype "passive"))
      (node (ref "LED13") (pin "A") (pinfunction "A_A") (pintype "passive"))
      (node (ref "LED3") (pin "A") (pinfunction "A_A") (pintype "passive"))
      (node (ref "LED4") (pin "A") (pinfunction "A_A") (pintype "passive"))
      (node (ref "LED6") (pin "A") (pinfunction "A_A") (pintype "passive"))
      (node (ref "LED7") (pin "A") (pinfunction "A_A") (pintype "passive"))
      (node (ref "LED8") (pin "A") (pinfunction "A_A") (pintype "passive"))
      (node (ref "LED9") (pin "A") (pinfunction "A_A") (pintype "passive"))
      (node (ref "TB1") (pin "VIN") (pinfunction "VIN_VIN") (pintype "passive"))
      (node (ref "TERA-DC/DC1") (pin "VIN") (pinfunction "VIN_VIN") (pintype "passive"))
      (node (ref "X1") (pin "2") (pinfunction "2_2") (pintype "passive"))
      (node (ref "X10") (pin "P$2") (pinfunction "2_P$2") (pintype "bidirectional"))
      (node (ref "X10") (pin "P$4") (pinfunction "4_P$4") (pintype "bidirectional"))
      (node (ref "X11") (pin "P$2") (pinfunction "2_P$2") (pintype "bidirectional"))
      (node (ref "X12") (pin "P$2") (pinfunction "2_P$2") (pintype "bidirectional"))
      (node (ref "X12") (pin "P$4") (pinfunction "4_P$4") (pintype "bidirectional"))
      (node (ref "X16") (pin "P$2") (pinfunction "2_P$2") (pintype "bidirectional"))
      (node (ref "X17") (pin "P$2") (pinfunction "2_P$2") (pintype "bidirectional"))
      (node (ref "X21") (pin "P$2") (pinfunction "2_P$2") (pintype "bidirectional"))
      (node (ref "X21") (pin "P$4") (pinfunction "4_P$4") (pintype "bidirectional"))
      (node (ref "X22") (pin "P$2") (pinfunction "2_P$2") (pintype "bidirectional"))
      (node (ref "X22") (pin "P$4") (pinfunction "4_P$4") (pintype "bidirectional"))
      (node (ref "X3") (pin "4") (pinfunction "V+_4") (pintype "passive"))
      (node (ref "X4") (pin "4") (pinfunction "V+_4") (pintype "passive"))
      (node (ref "X7") (pin "P$2") (pinfunction "2_P$2") (pintype "bidirectional"))
      (node (ref "X9") (pin "P$2") (pinfunction "2_P$2") (pintype "bidirectional"))
    )
    (net (code "4") (name "CAN1_H") (class "Default")
      (node (ref "C27") (pin "2") (pinfunction "2_2") (pintype "passive"))
      (node (ref "D12") (pin "1") (pinfunction "P$1_1") (pintype "passive"))
      (node (ref "L2") (pin "P$3") (pinfunction "3_P$3") (pintype "passive"))
      (node (ref "SW1") (pin "1") (pinfunction "1_1") (pintype "passive"))
      (node (ref "X3") (pin "3") (pinfunction "CANH_3") (pintype "passive"))
    )
    (net (code "5") (name "CAN1_H0") (class "Default")
      (node (ref "D4") (pin "1") (pinfunction "P$1_1") (pintype "passive"))
      (node (ref "IC2") (pin "7") (pinfunction "CANH_7") (pintype "bidirectional"))
      (node (ref "L2") (pin "P$4") (pinfunction "4_P$4") (pintype "passive"))
      (node (ref "SJ1") (pin "1") (pinfunction "1_1") (pintype "passive"))
    )
    (net (code "6") (name "CAN1_L") (class "Default")
      (node (ref "C27") (pin "1") (pinfunction "1_1") (pintype "passive"))
      (node (ref "D12") (pin "2") (pinfunction "P$2_2") (pintype "passive"))
      (node (ref "L2") (pin "P$1") (pinfunction "1_P$1") (pintype "passive"))
      (node (ref "SW1") (pin "2") (pinfunction "2_2") (pintype "passive"))
      (node (ref "X3") (pin "2") (pinfunction "CANL_2") (pintype "passive"))
    )
    (net (code "7") (name "CAN1_L0") (class "Default")
      (node (ref "D4") (pin "2") (pinfunction "P$2_2") (pintype "passive"))
      (node (ref "IC2") (pin "6") (pinfunction "CANL_6") (pintype "bidirectional"))
      (node (ref "L2") (pin "P$2") (pinfunction "2_P$2") (pintype "passive"))
      (node (ref "SJ2") (pin "1") (pinfunction "1_1") (pintype "passive"))
    )
    (net (code "8") (name "CAN1_RXD") (class "Default")
      (node (ref "IC2") (pin "4") (pinfunction "RXD_4") (pintype "output"))
      (node (ref "PROZ1") (pin "26") (pinfunction "PA11_26") (pintype "bidirectional"))
    )
    (net (code "9") (name "CAN1_TXD") (class "Default")
      (node (ref "IC2") (pin "1") (pinfunction "TXD_1") (pintype "input"))
      (node (ref "PROZ1") (pin "24") (pinfunction "PA12_24") (pintype "bidirectional"))
    )
    (net (code "10") (name "CAN2_H") (class "Default")
      (node (ref "C28") (pin "2") (pinfunction "2_2") (pintype "passive"))
      (node (ref "D13") (pin "2") (pinfunction "P$2_2") (pintype "passive"))
      (node (ref "L1") (pin "P$3") (pinfunction "3_P$3") (pintype "passive"))
      (node (ref "SW2") (pin "2") (pinfunction "2_2") (pintype "passive"))
      (node (ref "X4") (pin "3") (pinfunction "CANH_3") (pintype "passive"))
    )
    (net (code "11") (name "CAN2_H0") (class "Default")
      (node (ref "D3") (pin "1") (pinfunction "P$1_1") (pintype "passive"))
      (node (ref "IC1") (pin "7") (pinfunction "CANH_7") (pintype "bidirectional"))
      (node (ref "L1") (pin "P$4") (pinfunction "4_P$4") (pintype "passive"))
    )
    (net (code "12") (name "CAN2_L") (class "Default")
      (node (ref "C28") (pin "1") (pinfunction "1_1") (pintype "passive"))
      (node (ref "D13") (pin "1") (pinfunction "P$1_1") (pintype "passive"))
      (node (ref "L1") (pin "P$1") (pinfunction "1_P$1") (pintype "passive"))
      (node (ref "SW2") (pin "1") (pinfunction "1_1") (pintype "passive"))
      (node (ref "X4") (pin "2") (pinfunction "CANL_2") (pintype "passive"))
    )
    (net (code "13") (name "CAN2_L0") (class "Default")
      (node (ref "D3") (pin "2") (pinfunction "P$2_2") (pintype "passive"))
      (node (ref "IC1") (pin "6") (pinfunction "CANL_6") (pintype "bidirectional"))
      (node (ref "L1") (pin "P$2") (pinfunction "2_P$2") (pintype "passive"))
    )
    (net (code "14") (name "CAN2_RXD") (class "Default")
      (node (ref "IC1") (pin "4") (pinfunction "RXD_4") (pintype "output"))
      (node (ref "PROZ1") (pin "50") (pinfunction "PB12_50") (pintype "bidirectional"))
    )
    (net (code "15") (name "CAN2_TXD") (class "Default")
      (node (ref "IC1") (pin "1") (pinfunction "TXD_1") (pintype "input"))
      (node (ref "PROZ1") (pin "49") (pinfunction "PB13_49") (pintype "bidirectional"))
    )
    (net (code "16") (name "CANP_H") (class "Default")
      (node (ref "PROZ1") (pin "31") (pinfunction "CANH_31") (pintype "bidirectional"))
      (node (ref "SJ1") (pin "2") (pinfunction "2_2") (pintype "passive"))
    )
    (net (code "17") (name "CANP_L") (class "Default")
      (node (ref "PROZ1") (pin "32") (pinfunction "CANL_32") (pintype "bidirectional"))
      (node (ref "SJ2") (pin "2") (pinfunction "2_2") (pintype "passive"))
    )
    (net (code "18") (name "CS_B0") (class "Default")
      (node (ref "IC3") (pin "1") (pinfunction "A_1") (pintype "input"))
      (node (ref "PROZ1") (pin "43") (pinfunction "PA4_43") (pintype "bidirectional"))
    )
    (net (code "19") (name "CS_B1") (class "Default")
      (node (ref "IC3") (pin "2") (pinfunction "B_2") (pintype "input"))
      (node (ref "PROZ1") (pin "51") (pinfunction "PB15_51") (pintype "bidirectional"))
    )
    (net (code "20") (name "CS_B2") (class "Default")
      (node (ref "IC3") (pin "3") (pinfunction "C_3") (pintype "input"))
      (node (ref "PROZ1") (pin "52") (pinfunction "PC6_52") (pintype "bidirectional"))
    )
    (net (code "21") (name "FAN_CO1") (class "Default")
      (node (ref "IC4") (pin "4") (pinfunction "CO1_4") (pintype "bidirectional"))
      (node (ref "PROZ1") (pin "23") (pinfunction "PC13_23") (pintype "bidirectional"))
    )
    (net (code "22") (name "FAN_PWM") (class "Default")
      (node (ref "IC4") (pin "1") (pinfunction "IN2_1") (pintype "bidirectional"))
      (node (ref "IC4") (pin "7") (pinfunction "IN1_7") (pintype "bidirectional"))
      (node (ref "PROZ1") (pin "58") (pinfunction "PA10_58") (pintype "bidirectional"))
    )
    (net (code "23") (name "GND") (class "Default")
      (node (ref "C1") (pin "2") (pinfunction "2_2") (pintype "passive"))
      (node (ref "C10") (pin "2") (pinfunction "2_2") (pintype "passive"))
      (node (ref "C11") (pin "2") (pinfunction "2_2") (pintype "passive"))
      (node (ref "C12") (pin "2") (pinfunction "2_2") (pintype "passive"))
      (node (ref "C13") (pin "2") (pinfunction "2_2") (pintype "passive"))
      (node (ref "C14") (pin "2") (pinfunction "2_2") (pintype "passive"))
      (node (ref "C15") (pin "2") (pinfunction "2_2") (pintype "passive"))
      (node (ref "C16") (pin "2") (pinfunction "2_2") (pintype "passive"))
      (node (ref "C17") (pin "2") (pinfunction "2_2") (pintype "passive"))
      (node (ref "C18") (pin "2") (pinfunction "2_2") (pintype "passive"))
      (node (ref "C19") (pin "2") (pinfunction "2_2") (pintype "passive"))
      (node (ref "C2") (pin "2") (pinfunction "2_2") (pintype "passive"))
      (node (ref "C22") (pin "2") (pinfunction "2_2") (pintype "passive"))
      (node (ref "C23") (pin "1") (pinfunction "1_1") (pintype "passive"))
      (node (ref "C24") (pin "2") (pinfunction "2_2") (pintype "passive"))
      (node (ref "C3") (pin "2") (pinfunction "2_2") (pintype "passive"))
      (node (ref "C4") (pin "2") (pinfunction "2_2") (pintype "passive"))
      (node (ref "C5") (pin "2") (pinfunction "2_2") (pintype "passive"))
      (node (ref "C6") (pin "2") (pinfunction "2_2") (pintype "passive"))
      (node (ref "C7") (pin "1") (pinfunction "1_1") (pintype "passive"))
      (node (ref "C8") (pin "2") (pinfunction "2_2") (pintype "passive"))
      (node (ref "C9") (pin "2") (pinfunction "2_2") (pintype "passive"))
      (node (ref "D1") (pin "P$1") (pinfunction "P$1_P$1") (pintype "bidirectional"))
      (node (ref "D1") (pin "P$11") (pinfunction "P$1_P$11") (pintype "bidirectional"))
      (node (ref "D10") (pin "P$1") (pinfunction "P$1_P$1") (pintype "bidirectional"))
      (node (ref "D10") (pin "P$11") (pinfunction "P$1_P$11") (pintype "bidirectional"))
      (node (ref "D11") (pin "P$1") (pinfunction "P$1_P$1") (pintype "bidirectional"))
      (node (ref "D11") (pin "P$11") (pinfunction "P$1_P$11") (pintype "bidirectional"))
      (node (ref "D12") (pin "3") (pinfunction "P$3_3") (pintype "passive"))
      (node (ref "D13") (pin "3") (pinfunction "P$3_3") (pintype "passive"))
      (node (ref "D14") (pin "A") (pinfunction "A_A") (pintype "passive"))
      (node (ref "D3") (pin "3") (pinfunction "P$3_3") (pintype "passive"))
      (node (ref "D4") (pin "3") (pinfunction "P$3_3") (pintype "passive"))
      (node (ref "D5") (pin "P$1") (pinfunction "P$1_P$1") (pintype "bidirectional"))
      (node (ref "D5") (pin "P$11") (pinfunction "P$1_P$11") (pintype "bidirectional"))
      (node (ref "D6") (pin "P$1") (pinfunction "P$1_P$1") (pintype "bidirectional"))
      (node (ref "D6") (pin "P$11") (pinfunction "P$1_P$11") (pintype "bidirectional"))
      (node (ref "D7") (pin "P$1") (pinfunction "P$1_P$1") (pintype "bidirectional"))
      (node (ref "D7") (pin "P$11") (pinfunction "P$1_P$11") (pintype "bidirectional"))
      (node (ref "D8") (pin "P$1") (pinfunction "P$1_P$1") (pintype "bidirectional"))
      (node (ref "D8") (pin "P$11") (pinfunction "P$1_P$11") (pintype "bidirectional"))
      (node (ref "D9") (pin "P$1") (pinfunction "P$1_P$1") (pintype "bidirectional"))
      (node (ref "D9") (pin "P$11") (pinfunction "P$1_P$11") (pintype "bidirectional"))
      (node (ref "IC1") (pin "2") (pinfunction "GND_2") (pintype "power_in"))
      (node (ref "IC10") (pin "2") (pinfunction "GND_2") (pintype "bidirectional"))
      (node (ref "IC11") (pin "4") (pinfunction "GND_4") (pintype "power_in"))
      (node (ref "IC15") (pin "12") (pinfunction "GND2_12") (pintype "bidirectional"))
      (node (ref "IC15") (pin "13") (pinfunction "HEAT_13") (pintype "bidirectional"))
      (node (ref "IC15") (pin "6") (pinfunction "GND1_6") (pintype "bidirectional"))
      (node (ref "IC2") (pin "2") (pinfunction "GND_2") (pintype "power_in"))
      (node (ref "IC3") (pin "4") (pinfunction "G2A_4") (pintype "input"))
      (node (ref "IC3") (pin "5") (pinfunction "G2B_5") (pintype "input"))
      (node (ref "IC3") (pin "8") (pinfunction "GND_8") (pintype "power_in"))
      (node (ref "IC4") (pin "12") (pinfunction "GND2_12") (pintype "bidirectional"))
      (node (ref "IC4") (pin "13") (pinfunction "HEAT_13") (pintype "bidirectional"))
      (node (ref "IC4") (pin "6") (pinfunction "GND1_6") (pintype "bidirectional"))
      (node (ref "IC5") (pin "15") (pinfunction "GND21_15") (pintype "bidirectional"))
      (node (ref "IC5") (pin "2") (pinfunction "GND11_2") (pintype "bidirectional"))
      (node (ref "IC5") (pin "8") (pinfunction "GND12_8") (pintype "bidirectional"))
      (node (ref "IC5") (pin "9") (pinfunction "GND22_9") (pintype "bidirectional"))
      (node (ref "IC6") (pin "12") (pinfunction "GND2_12") (pintype "bidirectional"))
      (node (ref "IC6") (pin "13") (pinfunction "HEAT_13") (pintype "bidirectional"))
      (node (ref "IC6") (pin "6") (pinfunction "GND1_6") (pintype "bidirectional"))
      (node (ref "IC7") (pin "12") (pinfunction "GND2_12") (pintype "bidirectional"))
      (node (ref "IC7") (pin "13") (pinfunction "HEAT_13") (pintype "bidirectional"))
      (node (ref "IC7") (pin "6") (pinfunction "GND1_6") (pintype "bidirectional"))
      (node (ref "IC8") (pin "2") (pinfunction "GND_2") (pintype "bidirectional"))
      (node (ref "IC9") (pin "2") (pinfunction "GND_2") (pintype "bidirectional"))
      (node (ref "PROZ1") (pin "47") (pinfunction "GND_47") (pintype "passive"))
      (node (ref "PROZ1") (pin "48") (pinfunction "GND_48") (pintype "passive"))
      (node (ref "Q12") (pin "2") (pinfunction "S_2") (pintype "passive"))
      (node (ref "Q13") (pin "2") (pinfunction "S_2") (pintype "passive"))
      (node (ref "Q3") (pin "2") (pinfunction "S_2") (pintype "passive"))
      (node (ref "Q4") (pin "2") (pinfunction "S_2") (pintype "passive"))
      (node (ref "R1") (pin "1") (pinfunction "1_1") (pintype "passive"))
      (node (ref "R10") (pin "1") (pinfunction "1_1") (pintype "passive"))
      (node (ref "R11") (pin "1") (pinfunction "1_1") (pintype "passive"))
      (node (ref "R2") (pin "1") (pinfunction "1_1") (pintype "passive"))
      (node (ref "R20") (pin "1") (pinfunction "1_1") (pintype "passive"))
      (node (ref "R23") (pin "1") (pinfunction "1_1") (pintype "passive"))
      (node (ref "R27") (pin "2") (pinfunction "2_2") (pintype "passive"))
      (node (ref "R29") (pin "2") (pinfunction "2_2") (pintype "passive"))
      (node (ref "R3") (pin "1") (pinfunction "1_1") (pintype "passive"))
      (node (ref "R32") (pin "2") (pinfunction "2_2") (pintype "passive"))
      (node (ref "R34") (pin "2") (pinfunction "2_2") (pintype "passive"))
      (node (ref "R4") (pin "1") (pinfunction "1_1") (pintype "passive"))
      (node (ref "R56") (pin "2") (pinfunction "2_2") (pintype "passive"))
      (node (ref "R57") (pin "2") (pinfunction "2_2") (pintype "passive"))
      (node (ref "R58") (pin "2") (pinfunction "2_2") (pintype "passive"))
      (node (ref "R63") (pin "1") (pinfunction "1_1") (pintype "passive"))
      (node (ref "R77") (pin "1") (pinfunction "1_1") (pintype "passive"))
      (node (ref "R78") (pin "1") (pinfunction "1_1") (pintype "passive"))
      (node (ref "R9") (pin "1") (pinfunction "1_1") (pintype "passive"))
      (node (ref "TB1") (pin "GND") (pinfunction "GND_GND") (pintype "power_in"))
      (node (ref "TB1") (pin "GND2") (pinfunction "GND_GND2") (pintype "power_in"))
      (node (ref "TERA-DC/DC1") (pin "GND@1") (pinfunction "GND_GND@1") (pintype "power_in"))
      (node (ref "TERA-DC/DC1") (pin "GND@2") (pinfunction "GND_GND@2") (pintype "power_in"))
      (node (ref "X1") (pin "1") (pinfunction "1_1") (pintype "passive"))
      (node (ref "X13") (pin "1") (pinfunction "1_1") (pintype "passive"))
      (node (ref "X14") (pin "1") (pinfunction "1_1") (pintype "passive"))
      (node (ref "X15") (pin "1") (pinfunction "1_1") (pintype "passive"))
      (node (ref "X2") (pin "1") (pinfunction "GND_1") (pintype "passive"))
      (node (ref "X3") (pin "1") (pinfunction "GND_1") (pintype "passive"))
      (node (ref "X4") (pin "1") (pinfunction "GND_1") (pintype "passive"))
      (node (ref "X5") (pin "P$1") (pinfunction "1_P$1") (pintype "bidirectional"))
      (node (ref "X7") (pin "P$1") (pinfunction "1_P$1") (pintype "bidirectional"))
      (node (ref "X8") (pin "P$1") (pinfunction "1_P$1") (pintype "bidirectional"))
    )
    (net (code "24") (name "HS_CO1") (class "Default")
      (node (ref "IC7") (pin "4") (pinfunction "CO1_4") (pintype "bidirectional"))
      (node (ref "PROZ1") (pin "36") (pinfunction "PB2_36") (pintype "bidirectional"))
    )
    (net (code "25") (name "HS_RM") (class "Default")
      (node (ref "PROZ1") (pin "37") (pinfunction "PB1_37") (pintype "bidirectional"))
      (node (ref "Q4") (pin "3") (pinfunction "D_3") (pintype "passive"))
      (node (ref "R21") (pin "1") (pinfunction "1_1") (pintype "passive"))
    )
    (net (code "26") (name "HS_RM_EX") (class "Default")
      (node (ref "R22") (pin "2") (pinfunction "2_2") (pintype "passive"))
      (node (ref "X11") (pin "P$3") (pinfunction "3_P$3") (pintype "bidirectional"))
    )
    (net (code "27") (name "IL1") (class "Default")
      (node (ref "PROZ1") (pin "14") (pinfunction "PB6_14") (pintype "bidirectional"))
      (node (ref "X5") (pin "P$3") (pinfunction "3_P$3") (pintype "bidirectional"))
    )
    (net (code "28") (name "IL2") (class "Default")
      (node (ref "PROZ1") (pin "12") (pinfunction "PB7_12") (pintype "bidirectional"))
      (node (ref "X5") (pin "P$2") (pinfunction "2_P$2") (pintype "bidirectional"))
    )
    (net (code "29") (name "INTERLOCK_OK") (class "Default")
      (node (ref "IC15") (pin "1") (pinfunction "IN2_1") (pintype "bidirectional"))
      (node (ref "IC15") (pin "7") (pinfunction "IN1_7") (pintype "bidirectional"))
      (node (ref "IC6") (pin "1") (pinfunction "IN2_1") (pintype "bidirectional"))
      (node (ref "IC6") (pin "7") (pinfunction "IN1_7") (pintype "bidirectional"))
      (node (ref "IC7") (pin "1") (pinfunction "IN2_1") (pintype "bidirectional"))
      (node (ref "IC7") (pin "7") (pinfunction "IN1_7") (pintype "bidirectional"))
      (node (ref "PROZ1") (pin "44") (pinfunction "PA3_44") (pintype "bidirectional"))
      (node (ref "R9") (pin "2") (pinfunction "2_2") (pintype "passive"))
      (node (ref "X5") (pin "P$4") (pinfunction "4_P$4") (pintype "bidirectional"))
    )
    (net (code "30") (name "JTCK") (class "Default")
      (node (ref "PROZ1") (pin "18") (pinfunction "PA14_18") (pintype "bidirectional"))
      (node (ref "X2") (pin "5") (pinfunction "JTCK_5") (pintype "passive"))
    )
    (net (code "31") (name "JTDI") (class "Default")
      (node (ref "PROZ1") (pin "16") (pinfunction "PA15_16") (pintype "bidirectional"))
      (node (ref "X2") (pin "6") (pinfunction "JTDI_6") (pintype "passive"))
    )
    (net (code "32") (name "JTDO") (class "Default")
      (node (ref "PROZ1") (pin "20") (pinfunction "PB3_20") (pintype "bidirectional"))
      (node (ref "X2") (pin "7") (pinfunction "JTDO_7") (pintype "passive"))
    )
    (net (code "33") (name "JTMS") (class "Default")
      (node (ref "PROZ1") (pin "59") (pinfunction "PA13_59") (pintype "bidirectional"))
      (node (ref "X2") (pin "3") (pinfunction "JTMS_3") (pintype "passive"))
    )
    (net (code "34") (name "JTNRST") (class "Default")
      (node (ref "PROZ1") (pin "22") (pinfunction "PB4_22") (pintype "bidirectional"))
      (node (ref "X2") (pin "8") (pinfunction "JTNRST_8") (pintype "passive"))
    )
    (net (code "35") (name "LED1") (class "Default")
      (node (ref "PROZ1") (pin "25") (pinfunction "PB5_25") (pintype "bidirectional"))
    )
    (net (code "36") (name "LED2") (class "Default")
      (node (ref "PROZ1") (pin "27") (pinfunction "PD2_27") (pintype "bidirectional"))
    )
    (net (code "37") (name "LED3") (class "Default")
      (node (ref "PROZ1") (pin "29") (pinfunction "PC12_29") (pintype "bidirectional"))
    )
    (net (code "38") (name "LEM_1") (class "Default")
      (node (ref "C18") (pin "1") (pinfunction "1_1") (pintype "passive"))
      (node (ref "D7") (pin "P$2") (pinfunction "P$2_P$2") (pintype "bidirectional"))
      (node (ref "PROZ1") (pin "15") (pinfunction "PC0_15") (pintype "bidirectional"))
      (node (ref "R26") (pin "2") (pinfunction "2_2") (pintype "passive"))
    )
    (net (code "39") (name "LEM_2") (class "Default")
      (node (ref "C17") (pin "1") (pinfunction "1_1") (pintype "passive"))
      (node (ref "D6") (pin "P$2") (pinfunction "P$2_P$2") (pintype "bidirectional"))
      (node (ref "PROZ1") (pin "13") (pinfunction "PC1_13") (pintype "bidirectional"))
      (node (ref "R25") (pin "2") (pinfunction "2_2") (pintype "passive"))
    )
    (net (code "40") (name "LEM_3") (class "Default")
      (node (ref "C16") (pin "1") (pinfunction "1_1") (pintype "passive"))
      (node (ref "D8") (pin "P$2") (pinfunction "P$2_P$2") (pintype "bidirectional"))
      (node (ref "PROZ1") (pin "11") (pinfunction "PC2_11") (pintype "bidirectional"))
      (node (ref "R24") (pin "2") (pinfunction "2_2") (pintype "passive"))
    )
    (net (code "41") (name "MISO") (class "Default")
      (node (ref "IC15") (pin "11") (pinfunction "MISO/ST2_11") (pintype "bidirectional"))
      (node (ref "IC4") (pin "11") (pinfunction "MISO/ST2_11") (pintype "bidirectional"))
      (node (ref "IC5") (pin "11") (pinfunction "IN_D_11") (pintype "bidirectional"))
      (node (ref "IC6") (pin "11") (pinfunction "MISO/ST2_11") (pintype "bidirectional"))
      (node (ref "IC7") (pin "11") (pinfunction "MISO/ST2_11") (pintype "bidirectional"))
      (node (ref "X8") (pin "P$7") (pinfunction "7_P$7") (pintype "bidirectional"))
    )
    (net (code "42") (name "MISO_M") (class "Default")
      (node (ref "IC5") (pin "6") (pinfunction "OUT_D_6") (pintype "bidirectional"))
      (node (ref "PROZ1") (pin "42") (pinfunction "PA6_42") (pintype "bidirectional"))
    )
    (net (code "43") (name "MOSI") (class "Default")
      (node (ref "IC15") (pin "2") (pinfunction "MOSI_2") (pintype "bidirectional"))
      (node (ref "IC4") (pin "2") (pinfunction "MOSI_2") (pintype "bidirectional"))
      (node (ref "IC5") (pin "13") (pinfunction "OUT_B_13") (pintype "bidirectional"))
      (node (ref "IC6") (pin "2") (pinfunction "MOSI_2") (pintype "bidirectional"))
      (node (ref "IC7") (pin "2") (pinfunction "MOSI_2") (pintype "bidirectional"))
      (node (ref "X8") (pin "P$6") (pinfunction "6_P$6") (pintype "bidirectional"))
    )
    (net (code "44") (name "MOSI_M") (class "Default")
      (node (ref "IC5") (pin "4") (pinfunction "IN_B_4") (pintype "bidirectional"))
      (node (ref "PROZ1") (pin "41") (pinfunction "PA7_41") (pintype "bidirectional"))
    )
    (net (code "45") (name "NALERT") (class "Default")
      (node (ref "PROZ1") (pin "35") (pinfunction "PB10_35") (pintype "bidirectional"))
      (node (ref "R11") (pin "2") (pinfunction "2_2") (pintype "passive"))
      (node (ref "X6") (pin "P$2") (pinfunction "2_P$2") (pintype "bidirectional"))
    )
    (net (code "46") (name "NCS1") (class "Default")
      (node (ref "IC3") (pin "15") (pinfunction "Y0_15") (pintype "output"))
      (node (ref "X8") (pin "P$5") (pinfunction "5_P$5") (pintype "bidirectional"))
    )
    (net (code "47") (name "NCS2") (class "Default")
      (node (ref "IC3") (pin "14") (pinfunction "Y1_14") (pintype "output"))
      (node (ref "X8") (pin "P$4") (pinfunction "4_P$4") (pintype "bidirectional"))
    )
    (net (code "48") (name "NCS3") (class "Default")
      (node (ref "IC3") (pin "13") (pinfunction "Y2_13") (pintype "output"))
      (node (ref "X8") (pin "P$3") (pinfunction "3_P$3") (pintype "bidirectional"))
    )
    (net (code "49") (name "NCS4") (class "Default")
      (node (ref "IC3") (pin "12") (pinfunction "Y3_12") (pintype "output"))
      (node (ref "X8") (pin "P$2") (pinfunction "2_P$2") (pintype "bidirectional"))
    )
    (net (code "50") (name "NCS5") (class "Default")
      (node (ref "IC3") (pin "11") (pinfunction "Y4_11") (pintype "output"))
      (node (ref "IC4") (pin "8") (pinfunction "NCS_8") (pintype "bidirectional"))
    )
    (net (code "51") (name "NCS6") (class "Default")
      (node (ref "IC3") (pin "10") (pinfunction "Y5_10") (pintype "output"))
      (node (ref "IC7") (pin "8") (pinfunction "NCS_8") (pintype "bidirectional"))
    )
    (net (code "52") (name "NCS7") (class "Default")
      (node (ref "IC3") (pin "9") (pinfunction "Y6_9") (pintype "output"))
      (node (ref "IC6") (pin "8") (pinfunction "NCS_8") (pintype "bidirectional"))
    )
    (net (code "53") (name "NCS8") (class "Default")
      (node (ref "IC15") (pin "8") (pinfunction "NCS_8") (pintype "bidirectional"))
      (node (ref "IC3") (pin "7") (pinfunction "Y7_7") (pintype "output"))
    )
    (net (code "54") (name "NFAULT") (class "Default")
      (node (ref "PROZ1") (pin "53") (pinfunction "PC7_53") (pintype "bidirectional"))
      (node (ref "R10") (pin "2") (pinfunction "2_2") (pintype "passive"))
      (node (ref "X6") (pin "P$1") (pinfunction "1_P$1") (pintype "bidirectional"))
    )
    (net (code "55") (name "NRST") (class "Default")
      (node (ref "PROZ1") (pin "17") (pinfunction "NRST_17") (pintype "bidirectional"))
      (node (ref "X2") (pin "4") (pinfunction "NRST_4") (pintype "passive"))
    )
    (net (code "56") (name "Net-(C4-Pad1)") (class "Default")
      (node (ref "C4") (pin "1") (pinfunction "1_1") (pintype "passive"))
      (node (ref "R5") (pin "1") (pinfunction "1_1") (pintype "passive"))
      (node (ref "R6") (pin "1") (pinfunction "1_1") (pintype "passive"))
    )
    (net (code "57") (name "Net-(C5-Pad1)") (class "Default")
      (node (ref "C5") (pin "1") (pinfunction "1_1") (pintype "passive"))
      (node (ref "R7") (pin "1") (pinfunction "1_1") (pintype "passive"))
      (node (ref "R8") (pin "1") (pinfunction "1_1") (pintype "passive"))
    )
    (net (code "58") (name "Net-(CON2-Pad1)") (class "Default")
      (node (ref "CON2") (pin "1") (pinfunction "1_1") (pintype "passive"))
      (node (ref "R30") (pin "1") (pinfunction "1_1") (pintype "passive"))
    )
    (net (code "59") (name "Net-(CON3-Pad1)") (class "Default")
      (node (ref "CON3") (pin "1") (pinfunction "1_1") (pintype "passive"))
      (node (ref "R28") (pin "1") (pinfunction "1_1") (pintype "passive"))
    )
    (net (code "60") (name "Net-(CON4-Pad1)") (class "Default")
      (node (ref "CON4") (pin "1") (pinfunction "1_1") (pintype "passive"))
      (node (ref "R31") (pin "1") (pinfunction "1_1") (pintype "passive"))
    )
    (net (code "61") (name "Net-(CON5-Pad1)") (class "Default")
      (node (ref "CON5") (pin "1") (pinfunction "1_1") (pintype "passive"))
      (node (ref "R33") (pin "1") (pinfunction "1_1") (pintype "passive"))
    )
    (net (code "62") (name "Net-(IC1-RS)") (class "Default")
      (node (ref "IC1") (pin "8") (pinfunction "RS_8") (pintype "passive"))
      (node (ref "R3") (pin "2") (pinfunction "2_2") (pintype "passive"))
    )
    (net (code "63") (name "Net-(IC2-RS)") (class "Default")
      (node (ref "IC2") (pin "8") (pinfunction "RS_8") (pintype "passive"))
      (node (ref "R4") (pin "2") (pinfunction "2_2") (pintype "passive"))
    )
    (net (code "64") (name "Net-(IC2-VCC)") (class "Default")
      (node (ref "C2") (pin "1") (pinfunction "1_1") (pintype "passive"))
      (node (ref "IC2") (pin "3") (pinfunction "VCC_3") (pintype "power_in"))
      (node (ref "J3") (pin "P$2") (pinfunction "P$2_P$2") (pintype "bidirectional"))
    )
    (net (code "65") (name "Net-(IC4-OUT1)") (class "Default")
      (node (ref "IC4") (pin "9") (pinfunction "OUT1_9") (pintype "bidirectional"))
      (node (ref "R12") (pin "1") (pinfunction "1_1") (pintype "passive"))
      (node (ref "X16") (pin "P$1") (pinfunction "1_P$1") (pintype "bidirectional"))
    )
    (net (code "66") (name "Net-(IC4-OUT2)") (class "Default")
      (node (ref "IC4") (pin "3") (pinfunction "OUT2_3") (pintype "bidirectional"))
      (node (ref "R13") (pin "1") (pinfunction "1_1") (pintype "passive"))
      (node (ref "X17") (pin "P$1") (pinfunction "1_P$1") (pintype "bidirectional"))
    )
    (net (code "67") (name "Net-(IC6-OUT1)") (class "Default")
      (node (ref "IC6") (pin "9") (pinfunction "OUT1_9") (pintype "bidirectional"))
      (node (ref "R61") (pin "1") (pinfunction "1_1") (pintype "passive"))
      (node (ref "X10") (pin "P$1") (pinfunction "1_P$1") (pintype "bidirectional"))
    )
    (net (code "68") (name "Net-(IC6-OUT2)") (class "Default")
      (node (ref "IC6") (pin "3") (pinfunction "OUT2_3") (pintype "bidirectional"))
      (node (ref "R62") (pin "1") (pinfunction "1_1") (pintype "passive"))
      (node (ref "X9") (pin "P$1") (pinfunction "1_P$1") (pintype "bidirectional"))
    )
    (net (code "69") (name "Net-(IC7-OUT1)") (class "Default")
      (node (ref "IC7") (pin "9") (pinfunction "OUT1_9") (pintype "bidirectional"))
      (node (ref "R59") (pin "1") (pinfunction "1_1") (pintype "passive"))
      (node (ref "X12") (pin "P$1") (pinfunction "1_P$1") (pintype "bidirectional"))
    )
    (net (code "70") (name "Net-(IC7-OUT2)") (class "Default")
      (node (ref "IC7") (pin "3") (pinfunction "OUT2_3") (pintype "bidirectional"))
      (node (ref "R60") (pin "1") (pinfunction "1_1") (pintype "passive"))
      (node (ref "X11") (pin "P$1") (pinfunction "1_P$1") (pintype "bidirectional"))
    )
    (net (code "71") (name "Net-(IC8-VREF)") (class "Default")
      (node (ref "C13") (pin "1") (pinfunction "1_1") (pintype "passive"))
      (node (ref "IC8") (pin "5") (pinfunction "VREF_5") (pintype "bidirectional"))
      (node (ref "R58") (pin "1") (pinfunction "1_1") (pintype "passive"))
      (node (ref "X13") (pin "3") (pinfunction "3_3") (pintype "passive"))
    )
    (net (code "72") (name "Net-(IC9-VREF)") (class "Default")
      (node (ref "C14") (pin "1") (pinfunction "1_1") (pintype "passive"))
      (node (ref "IC9") (pin "5") (pinfunction "VREF_5") (pintype "bidirectional"))
      (node (ref "R57") (pin "1") (pinfunction "1_1") (pintype "passive"))
      (node (ref "X14") (pin "3") (pinfunction "3_3") (pintype "passive"))
    )
    (net (code "73") (name "Net-(IC10-VREF)") (class "Default")
      (node (ref "C15") (pin "1") (pinfunction "1_1") (pintype "passive"))
      (node (ref "IC10") (pin "5") (pinfunction "VREF_5") (pintype "bidirectional"))
      (node (ref "R56") (pin "1") (pinfunction "1_1") (pintype "passive"))
      (node (ref "X15") (pin "3") (pinfunction "3_3") (pintype "passive"))
    )
    (net (code "74") (name "Net-(IC15-OUT1)") (class "Default")
      (node (ref "IC15") (pin "9") (pinfunction "OUT1_9") (pintype "bidirectional"))
      (node (ref "R71") (pin "1") (pinfunction "1_1") (pintype "passive"))
      (node (ref "X21") (pin "P$1") (pinfunction "1_P$1") (pintype "bidirectional"))
    )
    (net (code "75") (name "Net-(IC15-OUT2)") (class "Default")
      (node (ref "IC15") (pin "3") (pinfunction "OUT2_3") (pintype "bidirectional"))
      (node (ref "R72") (pin "1") (pinfunction "1_1") (pintype "passive"))
      (node (ref "X22") (pin "P$1") (pinfunction "1_P$1") (pintype "bidirectional"))
    )
    (net (code "76") (name "Net-(LED1-PadC)") (class "Default")
      (node (ref "LED1") (pin "C") (pinfunction "C_C") (pintype "passive"))
      (node (ref "R1") (pin "2") (pinfunction "2_2") (pintype "passive"))
    )
    (net (code "77") (name "Net-(LED2-PadC)") (class "Default")
      (node (ref "LED2") (pin "C") (pinfunction "C_C") (pintype "passive"))
      (node (ref "R2") (pin "2") (pinfunction "2_2") (pintype "passive"))
    )
    (net (code "78") (name "Net-(LED3-PadC)") (class "Default")
      (node (ref "LED3") (pin "C") (pinfunction "C_C") (pintype "passive"))
      (node (ref "R12") (pin "2") (pinfunction "2_2") (pintype "passive"))
    )
    (net (code "79") (name "Net-(LED4-PadC)") (class "Default")
      (node (ref "LED4") (pin "C") (pinfunction "C_C") (pintype "passive"))
      (node (ref "R13") (pin "2") (pinfunction "2_2") (pintype "passive"))
    )
    (net (code "80") (name "Net-(LED6-PadC)") (class "Default")
      (node (ref "LED6") (pin "C") (pinfunction "C_C") (pintype "passive"))
      (node (ref "R59") (pin "2") (pinfunction "2_2") (pintype "passive"))
    )
    (net (code "81") (name "Net-(LED7-PadC)") (class "Default")
      (node (ref "LED7") (pin "C") (pinfunction "C_C") (pintype "passive"))
      (node (ref "R60") (pin "2") (pinfunction "2_2") (pintype "passive"))
    )
    (net (code "82") (name "Net-(LED8-PadC)") (class "Default")
      (node (ref "LED8") (pin "C") (pinfunction "C_C") (pintype "passive"))
      (node (ref "R61") (pin "2") (pinfunction "2_2") (pintype "passive"))
    )
    (net (code "83") (name "Net-(LED9-PadC)") (class "Default")
      (node (ref "LED9") (pin "C") (pinfunction "C_C") (pintype "passive"))
      (node (ref "R62") (pin "2") (pinfunction "2_2") (pintype "passive"))
    )
    (net (code "84") (name "Net-(LED10-PadC)") (class "Default")
      (node (ref "LED10") (pin "C") (pinfunction "C_C") (pintype "passive"))
      (node (ref "R63") (pin "2") (pinfunction "2_2") (pintype "passive"))
    )
    (net (code "85") (name "Net-(LED12-PadC)") (class "Default")
      (node (ref "LED12") (pin "C") (pinfunction "C_C") (pintype "passive"))
      (node (ref "R71") (pin "2") (pinfunction "2_2") (pintype "passive"))
    )
    (net (code "86") (name "Net-(LED13-PadC)") (class "Default")
      (node (ref "LED13") (pin "C") (pinfunction "C_C") (pintype "passive"))
      (node (ref "R72") (pin "2") (pinfunction "2_2") (pintype "passive"))
    )
    (net (code "87") (name "Net-(Q3-G)") (class "Default")
      (node (ref "Q3") (pin "1") (pinfunction "G_1") (pintype "passive"))
      (node (ref "R19") (pin "1") (pinfunction "1_1") (pintype "passive"))
      (node (ref "R20") (pin "2") (pinfunction "2_2") (pintype "passive"))
    )
    (net (code "88") (name "Net-(Q4-G)") (class "Default")
      (node (ref "Q4") (pin "1") (pinfunction "G_1") (pintype "passive"))
      (node (ref "R22") (pin "1") (pinfunction "1_1") (pintype "passive"))
      (node (ref "R23") (pin "2") (pinfunction "2_2") (pintype "passive"))
    )
    (net (code "89") (name "Net-(Q12-G)") (class "Default")
      (node (ref "Q12") (pin "1") (pinfunction "G_1") (pintype "passive"))
      (node (ref "R76") (pin "1") (pinfunction "1_1") (pintype "passive"))
      (node (ref "R78") (pin "2") (pinfunction "2_2") (pintype "passive"))
    )
    (net (code "90") (name "Net-(Q13-G)") (class "Default")
      (node (ref "Q13") (pin "1") (pinfunction "G_1") (pintype "passive"))
      (node (ref "R74") (pin "1") (pinfunction "1_1") (pintype "passive"))
      (node (ref "R77") (pin "2") (pinfunction "2_2") (pintype "passive"))
    )
    (net (code "91") (name "Net-(R5-Pad2)") (class "Default")
      (node (ref "R5") (pin "2") (pinfunction "2_2") (pintype "passive"))
      (node (ref "SW2") (pin "3") (pinfunction "3_3") (pintype "passive"))
    )
    (net (code "92") (name "Net-(R6-Pad2)") (class "Default")
      (node (ref "R6") (pin "2") (pinfunction "2_2") (pintype "passive"))
      (node (ref "SW2") (pin "4") (pinfunction "4_4") (pintype "passive"))
    )
    (net (code "93") (name "Net-(R7-Pad2)") (class "Default")
      (node (ref "R7") (pin "2") (pinfunction "2_2") (pintype "passive"))
      (node (ref "SW1") (pin "4") (pinfunction "4_4") (pintype "passive"))
    )
    (net (code "94") (name "Net-(R8-Pad2)") (class "Default")
      (node (ref "R8") (pin "2") (pinfunction "2_2") (pintype "passive"))
      (node (ref "SW1") (pin "3") (pinfunction "3_3") (pintype "passive"))
    )
    (net (code "95") (name "Net-(R24-Pad1)") (class "Default")
      (node (ref "R24") (pin "1") (pinfunction "1_1") (pintype "passive"))
      (node (ref "X13") (pin "2") (pinfunction "2_2") (pintype "passive"))
    )
    (net (code "96") (name "Net-(R25-Pad1)") (class "Default")
      (node (ref "R25") (pin "1") (pinfunction "1_1") (pintype "passive"))
      (node (ref "X14") (pin "2") (pinfunction "2_2") (pintype "passive"))
    )
    (net (code "97") (name "Net-(R26-Pad1)") (class "Default")
      (node (ref "R26") (pin "1") (pinfunction "1_1") (pintype "passive"))
      (node (ref "X15") (pin "2") (pinfunction "2_2") (pintype "passive"))
    )
    (net (code "98") (name "Net-(X10-3)") (class "Default")
      (node (ref "X10") (pin "P$3") (pinfunction "3_P$3") (pintype "bidirectional"))
      (node (ref "X9") (pin "P$4") (pinfunction "4_P$4") (pintype "bidirectional"))
    )
    (net (code "99") (name "Net-(X11-4)") (class "Default")
      (node (ref "X11") (pin "P$4") (pinfunction "4_P$4") (pintype "bidirectional"))
      (node (ref "X12") (pin "P$3") (pinfunction "3_P$3") (pintype "bidirectional"))
    )
    (net (code "100") (name "PA0") (class "Default")
      (node (ref "PROZ1") (pin "7") (pinfunction "PA0_7") (pintype "bidirectional"))
    )
    (net (code "101") (name "PB8") (class "Default")
      (node (ref "PROZ1") (pin "10") (pinfunction "PB8_10") (pintype "bidirectional"))
    )
    (net (code "102") (name "PB9") (class "Default")
      (node (ref "PROZ1") (pin "8") (pinfunction "PB9_8") (pintype "bidirectional"))
    )
    (net (code "103") (name "PC3") (class "Default")
      (node (ref "PROZ1") (pin "9") (pinfunction "PC3_9") (pintype "bidirectional"))
    )
    (net (code "104") (name "PC9") (class "Default")
      (node (ref "PROZ1") (pin "55") (pinfunction "PC9_55") (pintype "bidirectional"))
    )
    (net (code "105") (name "PC14") (class "Default")
      (node (ref "PROZ1") (pin "21") (pinfunction "PC14_21") (pintype "bidirectional"))
    )
    (net (code "106") (name "PC15") (class "Default")
      (node (ref "PROZ1") (pin "19") (pinfunction "PC15_19") (pintype "bidirectional"))
    )
    (net (code "107") (name "RM_KVL1") (class "Default")
      (node (ref "PROZ1") (pin "33") (pinfunction "PB14_33") (pintype "bidirectional"))
      (node (ref "Q13") (pin "3") (pinfunction "D_3") (pintype "passive"))
      (node (ref "R73") (pin "1") (pinfunction "1_1") (pintype "passive"))
    )
    (net (code "108") (name "RM_KVL1_EX") (class "Default")
      (node (ref "R74") (pin "2") (pinfunction "2_2") (pintype "passive"))
      (node (ref "X21") (pin "P$3") (pinfunction "3_P$3") (pintype "bidirectional"))
    )
    (net (code "109") (name "RM_KVL2") (class "Default")
      (node (ref "PROZ1") (pin "34") (pinfunction "PB11_34") (pintype "bidirectional"))
      (node (ref "Q12") (pin "3") (pinfunction "D_3") (pintype "passive"))
      (node (ref "R75") (pin "1") (pinfunction "1_1") (pintype "passive"))
    )
    (net (code "110") (name "RM_KVL2_EX") (class "Default")
      (node (ref "R76") (pin "2") (pinfunction "2_2") (pintype "passive"))
      (node (ref "X22") (pin "P$3") (pinfunction "3_P$3") (pintype "bidirectional"))
    )
    (net (code "111") (name "SCLK") (class "Default")
      (node (ref "IC15") (pin "5") (pinfunction "SCLK_5") (pintype "bidirectional"))
      (node (ref "IC4") (pin "5") (pinfunction "SCLK_5") (pintype "bidirectional"))
      (node (ref "IC5") (pin "14") (pinfunction "OUT_A_14") (pintype "bidirectional"))
      (node (ref "IC6") (pin "5") (pinfunction "SCLK_5") (pintype "bidirectional"))
      (node (ref "IC7") (pin "5") (pinfunction "SCLK_5") (pintype "bidirectional"))
      (node (ref "X8") (pin "P$8") (pinfunction "8_P$8") (pintype "bidirectional"))
    )
    (net (code "112") (name "SCLK_M") (class "Default")
      (node (ref "IC5") (pin "3") (pinfunction "IN_A_3") (pintype "bidirectional"))
      (node (ref "PROZ1") (pin "60") (pinfunction "PA5_60") (pintype "bidirectional"))
    )
    (net (code "113") (name "SLS_CO1") (class "Default")
      (node (ref "IC6") (pin "4") (pinfunction "CO1_4") (pintype "bidirectional"))
      (node (ref "PROZ1") (pin "57") (pinfunction "PA9_57") (pintype "bidirectional"))
    )
    (net (code "114") (name "SLS_RM") (class "Default")
      (node (ref "PROZ1") (pin "56") (pinfunction "PA8_56") (pintype "bidirectional"))
      (node (ref "Q3") (pin "3") (pinfunction "D_3") (pintype "passive"))
      (node (ref "R18") (pin "1") (pinfunction "1_1") (pintype "passive"))
    )
    (net (code "115") (name "SLS_RM_EX") (class "Default")
      (node (ref "R19") (pin "2") (pinfunction "2_2") (pintype "passive"))
      (node (ref "X9") (pin "P$3") (pinfunction "3_P$3") (pintype "bidirectional"))
    )
    (net (code "116") (name "SPI_CS") (class "Default")
      (node (ref "IC3") (pin "6") (pinfunction "G1_6") (pintype "input"))
      (node (ref "PROZ1") (pin "38") (pinfunction "PB0_38") (pintype "bidirectional"))
    )
    (net (code "117") (name "TS1") (class "Default")
      (node (ref "C21") (pin "2") (pinfunction "2_2") (pintype "passive"))
      (node (ref "D9") (pin "P$2") (pinfunction "P$2_P$2") (pintype "bidirectional"))
      (node (ref "PROZ1") (pin "40") (pinfunction "PC4_40") (pintype "bidirectional"))
      (node (ref "R29") (pin "1") (pinfunction "1_1") (pintype "passive"))
      (node (ref "R30") (pin "2") (pinfunction "2_2") (pintype "passive"))
    )
    (net (code "118") (name "TS2") (class "Default")
      (node (ref "C20") (pin "2") (pinfunction "2_2") (pintype "passive"))
      (node (ref "D10") (pin "P$2") (pinfunction "P$2_P$2") (pintype "bidirectional"))
      (node (ref "PROZ1") (pin "39") (pinfunction "PC5_39") (pintype "bidirectional"))
      (node (ref "R27") (pin "1") (pinfunction "1_1") (pintype "passive"))
      (node (ref "R28") (pin "2") (pinfunction "2_2") (pintype "passive"))
    )
    (net (code "119") (name "TS3") (class "Default")
      (node (ref "C25") (pin "2") (pinfunction "2_2") (pintype "passive"))
      (node (ref "D1") (pin "P$2") (pinfunction "P$2_P$2") (pintype "bidirectional"))
      (node (ref "PROZ1") (pin "5") (pinfunction "PA1_5") (pintype "bidirectional"))
      (node (ref "R31") (pin "2") (pinfunction "2_2") (pintype "passive"))
      (node (ref "R32") (pin "1") (pinfunction "1_1") (pintype "passive"))
    )
    (net (code "120") (name "TS4") (class "Default")
      (node (ref "C26") (pin "2") (pinfunction "2_2") (pintype "passive"))
      (node (ref "D11") (pin "P$2") (pinfunction "P$2_P$2") (pintype "bidirectional"))
      (node (ref "PROZ1") (pin "3") (pinfunction "PA2_3") (pintype "bidirectional"))
      (node (ref "R33") (pin "2") (pinfunction "2_2") (pintype "passive"))
      (node (ref "R34") (pin "1") (pinfunction "1_1") (pintype "passive"))
    )
    (net (code "121") (name "USART_RXD") (class "Default")
      (node (ref "PROZ1") (pin "30") (pinfunction "PC11_30") (pintype "bidirectional"))
      (node (ref "X2") (pin "10") (pinfunction "RXD_10") (pintype "passive"))
    )
    (net (code "122") (name "USART_TXD") (class "Default")
      (node (ref "PROZ1") (pin "28") (pinfunction "PC10_28") (pintype "bidirectional"))
      (node (ref "X2") (pin "9") (pinfunction "TXD_9") (pintype "passive"))
    )
    (net (code "123") (name "VL_CO1") (class "Default")
      (node (ref "IC15") (pin "4") (pinfunction "CO1_4") (pintype "bidirectional"))
      (node (ref "PROZ1") (pin "54") (pinfunction "PC8_54") (pintype "bidirectional"))
    )
    (net (code "124") (name "VREF_PTC_CH") (class "Default")
      (node (ref "C20") (pin "1") (pinfunction "1_1") (pintype "passive"))
      (node (ref "C21") (pin "1") (pinfunction "1_1") (pintype "passive"))
      (node (ref "C22") (pin "1") (pinfunction "1_1") (pintype "passive"))
      (node (ref "C25") (pin "1") (pinfunction "1_1") (pintype "passive"))
      (node (ref "C26") (pin "1") (pinfunction "1_1") (pintype "passive"))
      (node (ref "CON2") (pin "2") (pinfunction "2_2") (pintype "passive"))
      (node (ref "CON3") (pin "2") (pinfunction "2_2") (pintype "passive"))
      (node (ref "CON4") (pin "2") (pinfunction "2_2") (pintype "passive"))
      (node (ref "CON5") (pin "2") (pinfunction "2_2") (pintype "passive"))
      (node (ref "IC11") (pin "6") (pinfunction "VOUT_6") (pintype "bidirectional"))
    )
    (net (code "125") (name "unconnected-(IC1-VREF-Pad5)") (class "Default")
      (node (ref "IC1") (pin "5") (pinfunction "VREF_5") (pintype "passive"))
    )
    (net (code "126") (name "unconnected-(IC2-VREF-Pad5)") (class "Default")
      (node (ref "IC2") (pin "5") (pinfunction "VREF_5") (pintype "passive"))
    )
    (net (code "127") (name "unconnected-(IC5-IN_C-Pad5)") (class "Default")
      (node (ref "IC5") (pin "5") (pinfunction "IN_C_5") (pintype "bidirectional"))
    )
    (net (code "128") (name "unconnected-(IC5-OUT_C-Pad12)") (class "Default")
      (node (ref "IC5") (pin "12") (pinfunction "OUT_C_12") (pintype "bidirectional"))
    )
    (net (code "129") (name "unconnected-(IC11-~{SHDN}-Pad3)") (class "Default")
      (node (ref "IC11") (pin "3") (pinfunction "~{SHDN}_3") (pintype "passive"))
    )
    (net (code "130") (name "unconnected-(J3-PadP$3)") (class "Default")
      (node (ref "J3") (pin "P$3") (pinfunction "P$3_P$3") (pintype "bidirectional"))
    )
    (net (code "131") (name "unconnected-(PROZ1F-AGND-Pad1)") (class "Default")
      (node (ref "PROZ1") (pin "1") (pinfunction "AGND_1") (pintype "passive"))
    )
    (net (code "132") (name "unconnected-(PROZ1F-VBAT-Pad6)") (class "Default")
      (node (ref "PROZ1") (pin "6") (pinfunction "VBAT_6") (pintype "passive"))
    )
    (net (code "133") (name "unconnected-(PROZ1F-VDDA_IN-Pad2)") (class "Default")
      (node (ref "PROZ1") (pin "2") (pinfunction "VDDA_IN_2") (pintype "passive"))
    )
    (net (code "134") (name "unconnected-(PROZ1F-VDDA_OUT-Pad4)") (class "Default")
      (node (ref "PROZ1") (pin "4") (pinfunction "VDDA_OUT_4") (pintype "passive"))
    )
  )
)
